# homeboard15.net
KiCad netlist of a schematic drawn in EAGLE
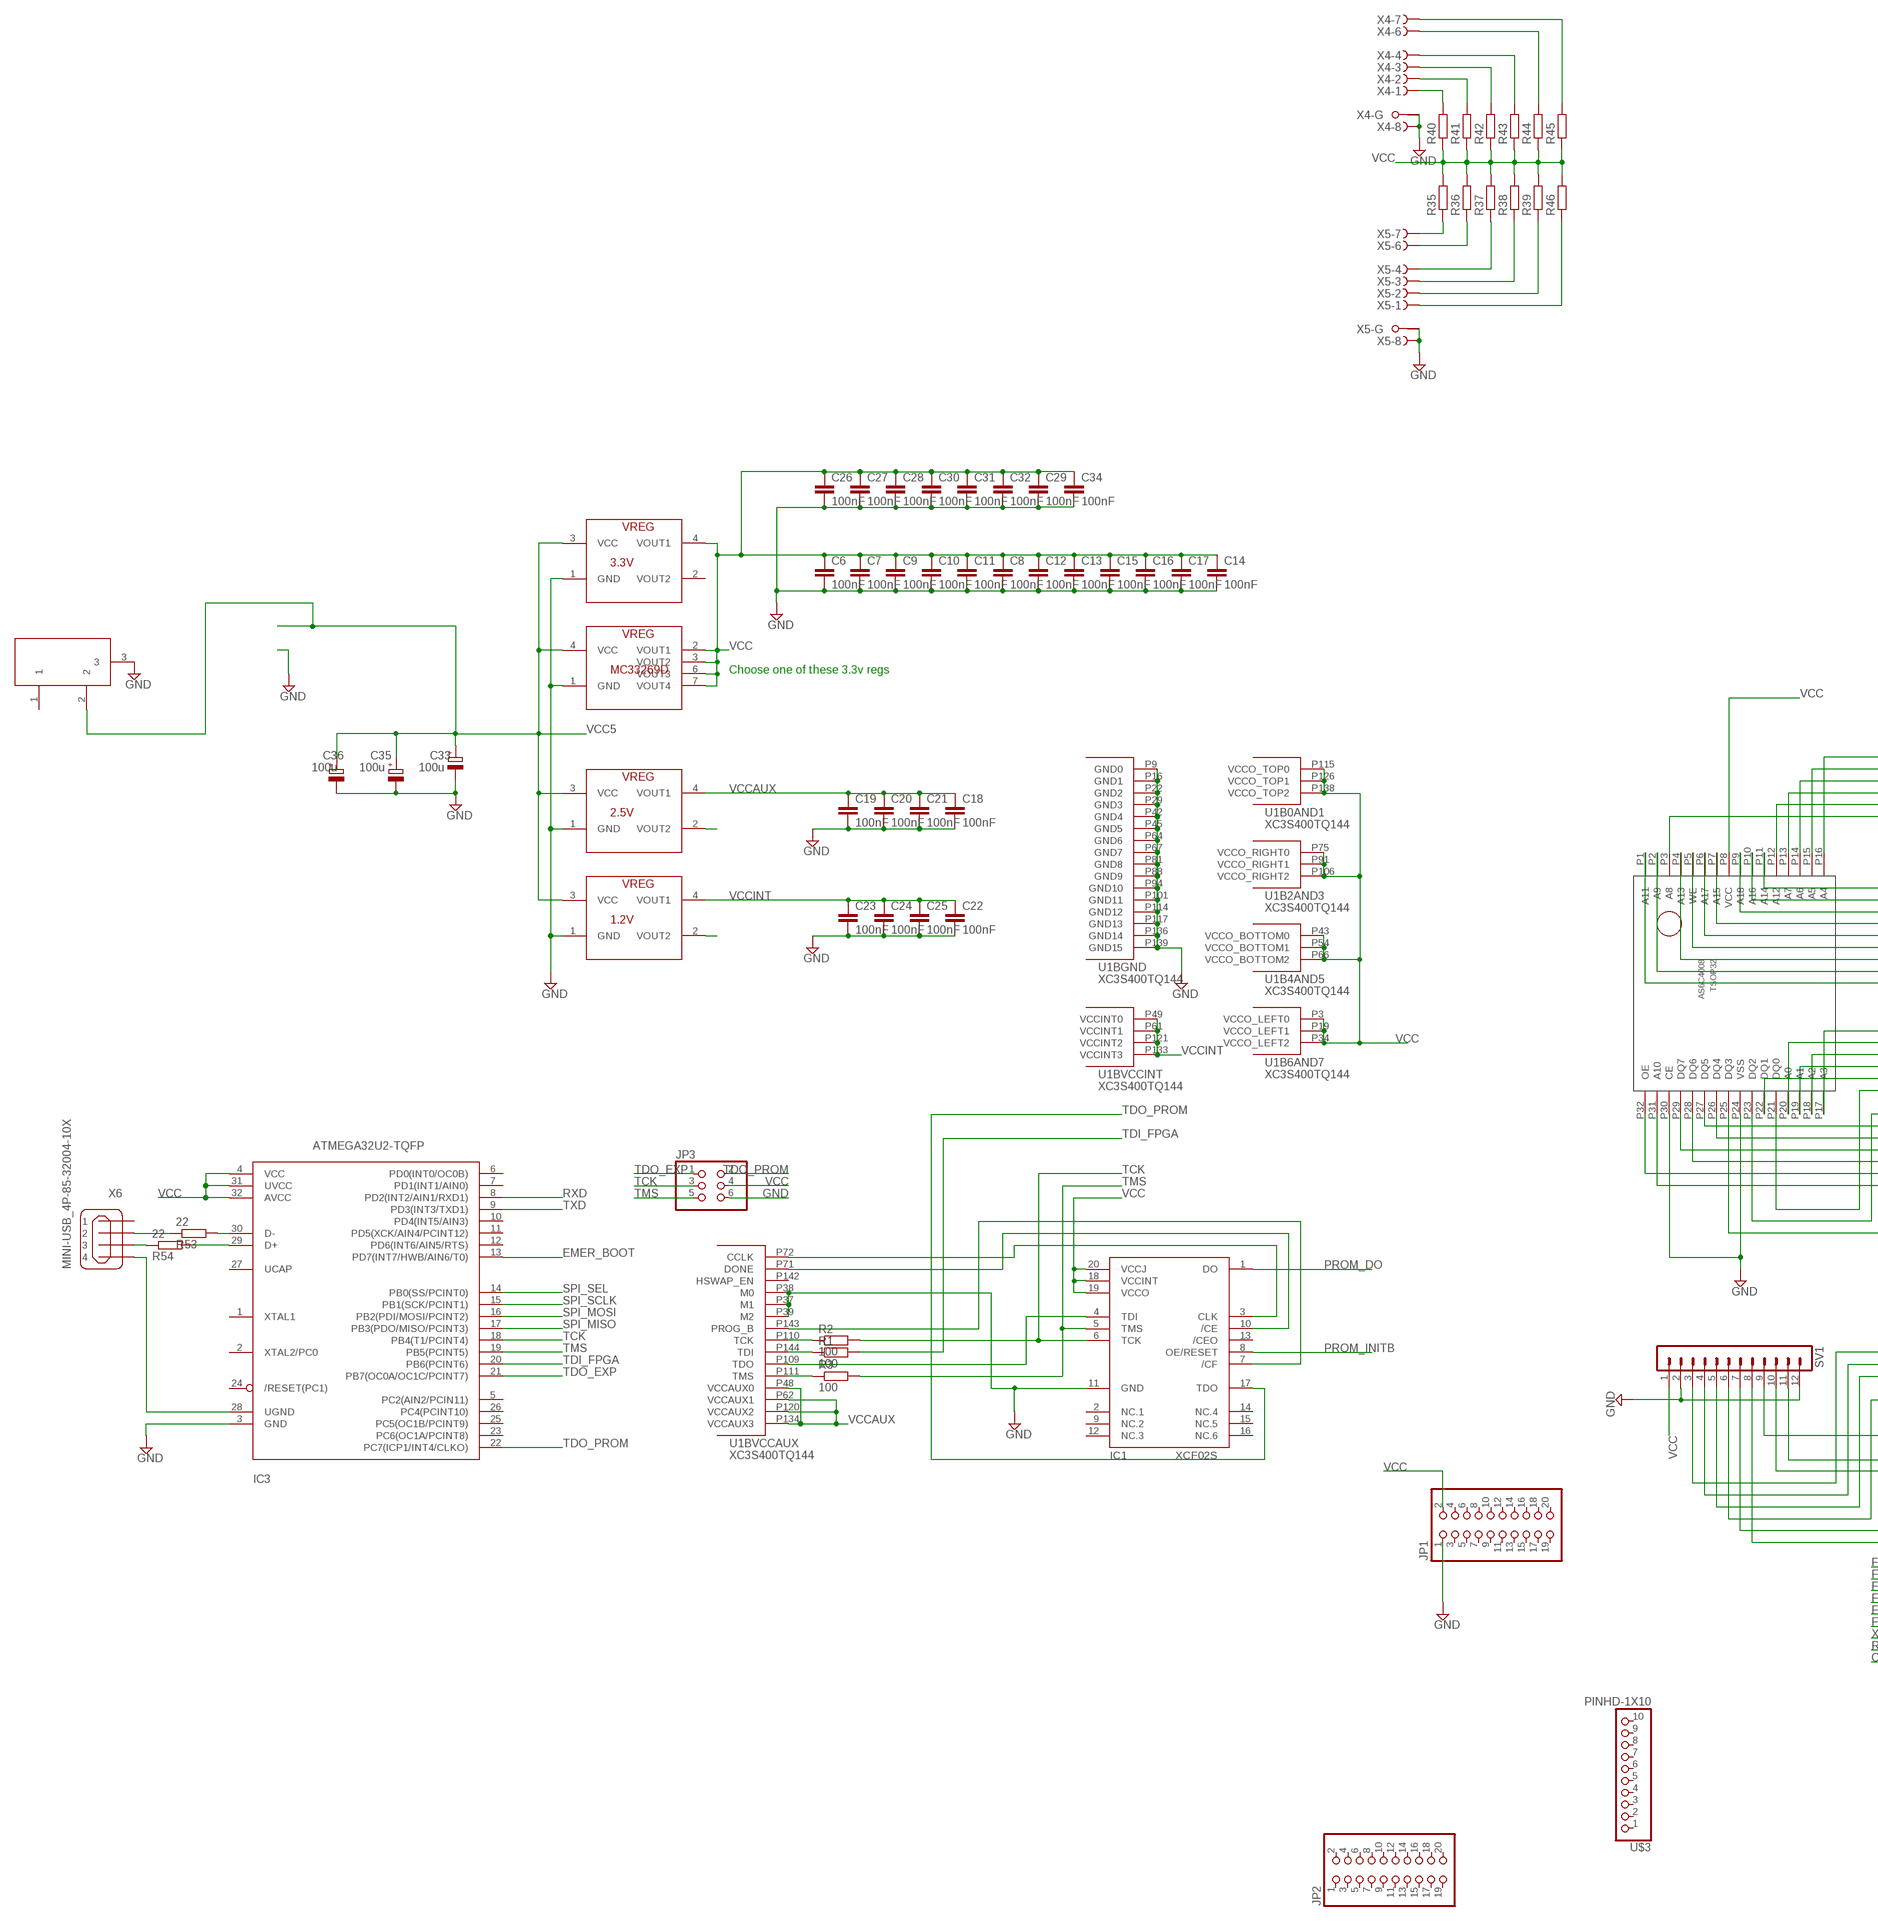
[diagram p0: schematic, sheet 1, part 1 of 3]
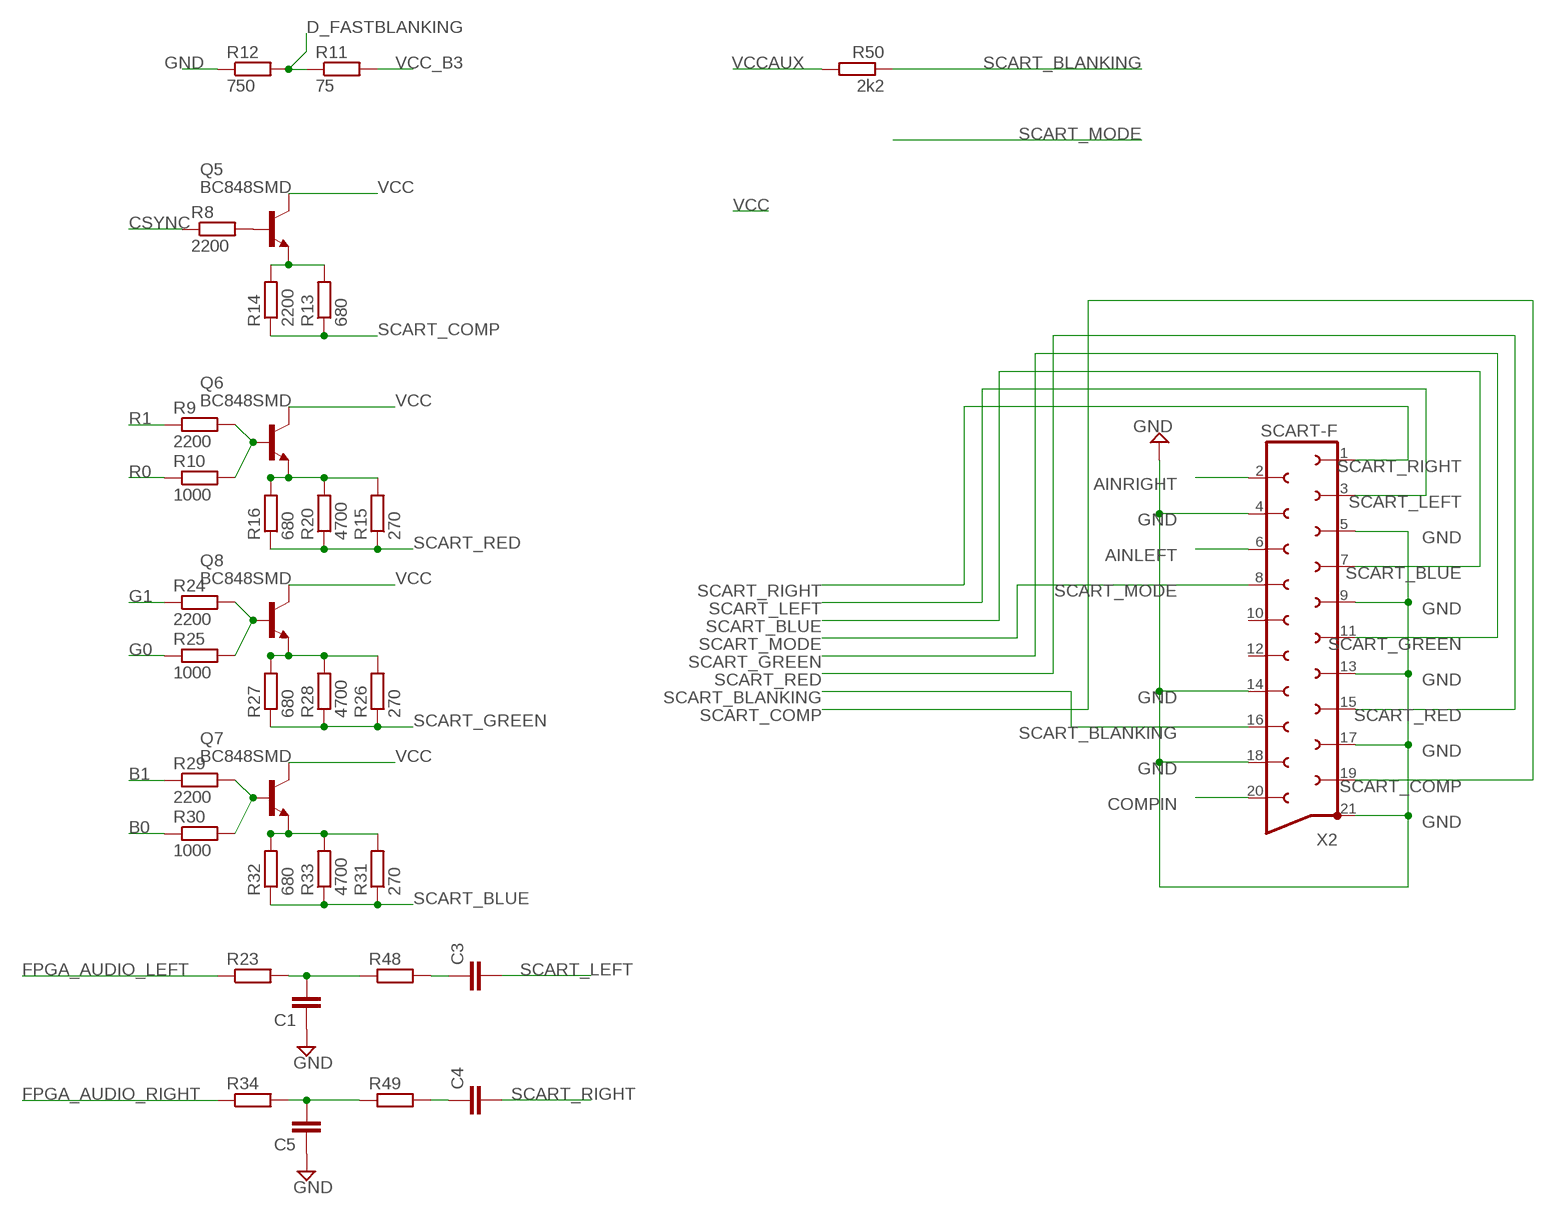
[diagram p1: schematic, sheet 1, part 2 of 3]
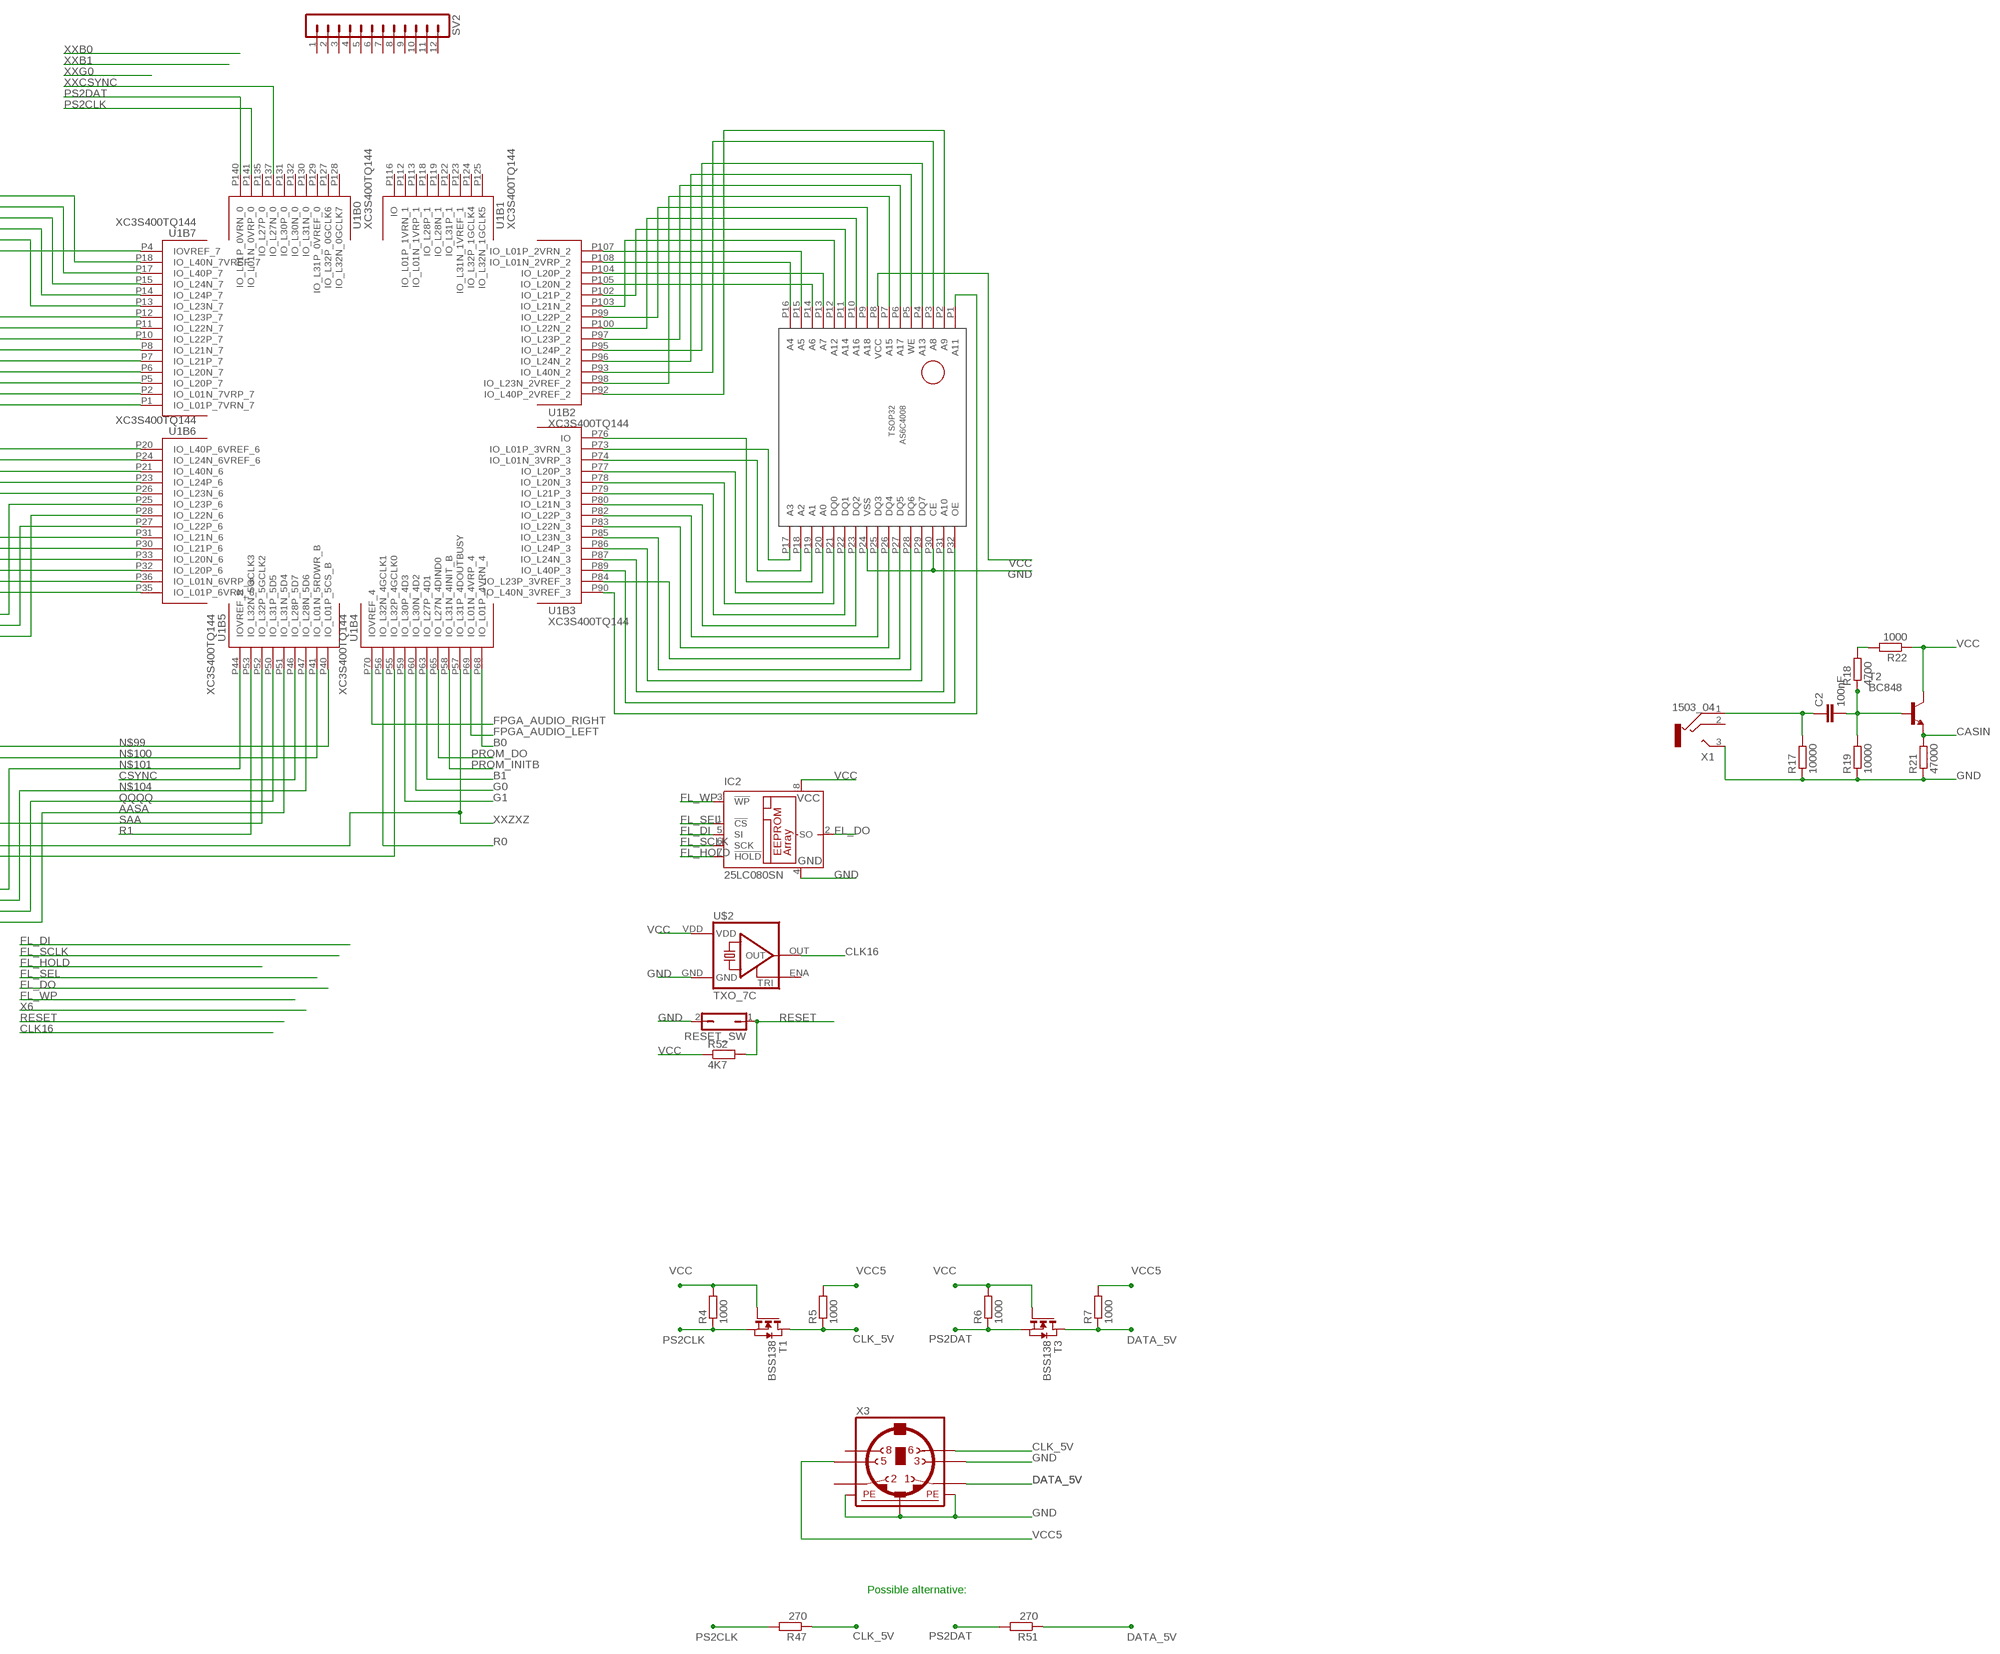
[diagram p2: schematic, sheet 1, part 3 of 3]

(export (version "E")
  (design (tool "Eeschema 10.0.6"))
  (components
    (comp (ref "C1")
      (value "C-EUC0603")
      (footprint "eagle-import:C0603")
      (libsource (lib "eagle-import") (part "resistor_C-EUC0603"))
    )
    (comp (ref "C2")
      (value "100nF")
      (footprint "eagle-import:C0603")
      (libsource (lib "eagle-import") (part "resistor_C-EUC0603"))
    )
    (comp (ref "C3")
      (value "C-EUC0603")
      (footprint "eagle-import:C0603")
      (libsource (lib "eagle-import") (part "resistor_C-EUC0603"))
    )
    (comp (ref "C4")
      (value "C-EUC0603")
      (footprint "eagle-import:C0603")
      (libsource (lib "eagle-import") (part "resistor_C-EUC0603"))
    )
    (comp (ref "C5")
      (value "C-EUC0603")
      (footprint "eagle-import:C0603")
      (libsource (lib "eagle-import") (part "resistor_C-EUC0603"))
    )
    (comp (ref "C6")
      (value "100nF")
      (footprint "eagle-import:C0603")
      (libsource (lib "eagle-import") (part "C-EUC0603"))
    )
    (comp (ref "C7")
      (value "100nF")
      (footprint "eagle-import:C0603")
      (libsource (lib "eagle-import") (part "C-EUC0603"))
    )
    (comp (ref "C8")
      (value "100nF")
      (footprint "eagle-import:C0603")
      (libsource (lib "eagle-import") (part "C-EUC0603"))
    )
    (comp (ref "C9")
      (value "100nF")
      (footprint "eagle-import:C0603")
      (libsource (lib "eagle-import") (part "C-EUC0603"))
    )
    (comp (ref "C10")
      (value "100nF")
      (footprint "eagle-import:C0603")
      (libsource (lib "eagle-import") (part "C-EUC0603"))
    )
    (comp (ref "C11")
      (value "100nF")
      (footprint "eagle-import:C0603")
      (libsource (lib "eagle-import") (part "C-EUC0603"))
    )
    (comp (ref "C12")
      (value "100nF")
      (footprint "eagle-import:C0603")
      (libsource (lib "eagle-import") (part "C-EUC0603"))
    )
    (comp (ref "C13")
      (value "100nF")
      (footprint "eagle-import:C0603")
      (libsource (lib "eagle-import") (part "C-EUC0603"))
    )
    (comp (ref "C14")
      (value "100nF")
      (footprint "eagle-import:C0603")
      (libsource (lib "eagle-import") (part "C-EUC0603"))
    )
    (comp (ref "C15")
      (value "100nF")
      (footprint "eagle-import:C0603")
      (libsource (lib "eagle-import") (part "C-EUC0603"))
    )
    (comp (ref "C16")
      (value "100nF")
      (footprint "eagle-import:C0603")
      (libsource (lib "eagle-import") (part "C-EUC0603"))
    )
    (comp (ref "C17")
      (value "100nF")
      (footprint "eagle-import:C0603")
      (libsource (lib "eagle-import") (part "C-EUC0603"))
    )
    (comp (ref "C18")
      (value "100nF")
      (footprint "eagle-import:C0603")
      (libsource (lib "eagle-import") (part "C-EUC0603"))
    )
    (comp (ref "C19")
      (value "100nF")
      (footprint "eagle-import:C0603")
      (libsource (lib "eagle-import") (part "C-EUC0603"))
    )
    (comp (ref "C20")
      (value "100nF")
      (footprint "eagle-import:C0603")
      (libsource (lib "eagle-import") (part "C-EUC0603"))
    )
    (comp (ref "C21")
      (value "100nF")
      (footprint "eagle-import:C0603")
      (libsource (lib "eagle-import") (part "C-EUC0603"))
    )
    (comp (ref "C22")
      (value "100nF")
      (footprint "eagle-import:C0603")
      (libsource (lib "eagle-import") (part "C-EUC0603"))
    )
    (comp (ref "C23")
      (value "100nF")
      (footprint "eagle-import:C0603")
      (libsource (lib "eagle-import") (part "C-EUC0603"))
    )
    (comp (ref "C24")
      (value "100nF")
      (footprint "eagle-import:C0603")
      (libsource (lib "eagle-import") (part "C-EUC0603"))
    )
    (comp (ref "C25")
      (value "100nF")
      (footprint "eagle-import:C0603")
      (libsource (lib "eagle-import") (part "C-EUC0603"))
    )
    (comp (ref "C26")
      (value "100nF")
      (footprint "eagle-import:C0603")
      (libsource (lib "eagle-import") (part "C-EUC0603"))
    )
    (comp (ref "C27")
      (value "100nF")
      (footprint "eagle-import:C0603")
      (libsource (lib "eagle-import") (part "C-EUC0603"))
    )
    (comp (ref "C28")
      (value "100nF")
      (footprint "eagle-import:C0603")
      (libsource (lib "eagle-import") (part "C-EUC0603"))
    )
    (comp (ref "C29")
      (value "100nF")
      (footprint "eagle-import:C0603")
      (libsource (lib "eagle-import") (part "C-EUC0603"))
    )
    (comp (ref "C30")
      (value "100nF")
      (footprint "eagle-import:C0603")
      (libsource (lib "eagle-import") (part "C-EUC0603"))
    )
    (comp (ref "C31")
      (value "100nF")
      (footprint "eagle-import:C0603")
      (libsource (lib "eagle-import") (part "C-EUC0603"))
    )
    (comp (ref "C32")
      (value "100nF")
      (footprint "eagle-import:C0603")
      (libsource (lib "eagle-import") (part "C-EUC0603"))
    )
    (comp (ref "C33")
      (value "100u")
      (footprint "eagle-import:PANASONIC_D")
      (libsource (lib "eagle-import") (part "CPOL-EUD"))
    )
    (comp (ref "C34")
      (value "100nF")
      (footprint "eagle-import:C0603")
      (libsource (lib "eagle-import") (part "C-EUC0603"))
    )
    (comp (ref "C35")
      (value "100u")
      (footprint "eagle-import:PANASONIC_D")
      (libsource (lib "eagle-import") (part "CPOL-EUD"))
    )
    (comp (ref "C36")
      (value "100u")
      (footprint "eagle-import:PANASONIC_D")
      (libsource (lib "eagle-import") (part "CPOL-EUD"))
    )
    (comp (ref "IC1")
      (value "XCF02S")
      (footprint "eagle-import:VO20")
      (libsource (lib "eagle-import") (part "XCF02S"))
    )
    (comp (ref "IC2")
      (value "25LC080SN")
      (footprint "eagle-import:SO-08")
      (fields (field (name "MF") "MICROCHIP") (field (name "MPN") "25LC080/SN"))
      (libsource (lib "eagle-import") (part "25SNLC080"))
    )
    (comp (ref "IC3")
      (value "ATMEGA32U2-TQFP")
      (footprint "eagle-import:TQFP32-08")
      (libsource (lib "eagle-import") (part "ATMEGA32U2-TQFP"))
    )
    (comp (ref "JP1")
      (value "PINHD-2X10")
      (footprint "eagle-import:2X10")
      (libsource (lib "eagle-import") (part "PINHD-2X10"))
    )
    (comp (ref "JP2")
      (value "PINHD-2X10")
      (footprint "eagle-import:2X10")
      (libsource (lib "eagle-import") (part "PINHD-2X10"))
    )
    (comp (ref "JP3")
      (value "PINHD-2X3")
      (footprint "eagle-import:2X03")
      (libsource (lib "eagle-import") (part "PINHD-2X3"))
    )
    (comp (ref "Q5")
      (value "BC848SMD")
      (footprint "eagle-import:SOT23")
      (libsource (lib "eagle-import") (part "BC848SMD"))
    )
    (comp (ref "Q6")
      (value "BC848SMD")
      (footprint "eagle-import:SOT23")
      (libsource (lib "eagle-import") (part "BC848SMD"))
    )
    (comp (ref "Q7")
      (value "BC848SMD")
      (footprint "eagle-import:SOT23")
      (libsource (lib "eagle-import") (part "BC848SMD"))
    )
    (comp (ref "Q8")
      (value "BC848SMD")
      (footprint "eagle-import:SOT23")
      (libsource (lib "eagle-import") (part "BC848SMD"))
    )
    (comp (ref "R1")
      (value "100")
      (footprint "eagle-import:R0805")
      (libsource (lib "eagle-import") (part "R-EU_R0805"))
    )
    (comp (ref "R2")
      (value "100")
      (footprint "eagle-import:R0805")
      (libsource (lib "eagle-import") (part "R-EU_R0805"))
    )
    (comp (ref "R3")
      (value "100")
      (footprint "eagle-import:R0805")
      (libsource (lib "eagle-import") (part "R-EU_R0805"))
    )
    (comp (ref "R4")
      (value "1000")
      (footprint "eagle-import:R0805")
      (libsource (lib "eagle-import") (part "R-EU_R0805"))
    )
    (comp (ref "R5")
      (value "1000")
      (footprint "eagle-import:R0805")
      (libsource (lib "eagle-import") (part "R-EU_R0805"))
    )
    (comp (ref "R6")
      (value "1000")
      (footprint "eagle-import:R0805")
      (libsource (lib "eagle-import") (part "R-EU_R0805"))
    )
    (comp (ref "R7")
      (value "1000")
      (footprint "eagle-import:R0805")
      (libsource (lib "eagle-import") (part "R-EU_R0805"))
    )
    (comp (ref "R8")
      (value "2200")
      (footprint "eagle-import:R0805")
      (libsource (lib "eagle-import") (part "R-EU_R0805"))
    )
    (comp (ref "R9")
      (value "2200")
      (footprint "eagle-import:R0805")
      (libsource (lib "eagle-import") (part "R-EU_R0805"))
    )
    (comp (ref "R10")
      (value "1000")
      (footprint "eagle-import:R0805")
      (libsource (lib "eagle-import") (part "R-EU_R0805"))
    )
    (comp (ref "R11")
      (value "75")
      (footprint "eagle-import:R0805")
      (libsource (lib "eagle-import") (part "R-EU_R0805"))
    )
    (comp (ref "R12")
      (value "750")
      (footprint "eagle-import:R0805")
      (libsource (lib "eagle-import") (part "R-EU_R0805"))
    )
    (comp (ref "R13")
      (value "680")
      (footprint "eagle-import:R0805")
      (libsource (lib "eagle-import") (part "R-EU_R0805"))
    )
    (comp (ref "R14")
      (value "2200")
      (footprint "eagle-import:R0805")
      (libsource (lib "eagle-import") (part "R-EU_R0805"))
    )
    (comp (ref "R15")
      (value "270")
      (footprint "eagle-import:R0805")
      (libsource (lib "eagle-import") (part "R-EU_R0805"))
    )
    (comp (ref "R16")
      (value "680")
      (footprint "eagle-import:R0805")
      (libsource (lib "eagle-import") (part "R-EU_R0805"))
    )
    (comp (ref "R17")
      (value "10000")
      (footprint "eagle-import:R0805")
      (libsource (lib "eagle-import") (part "R-EU_R0805"))
    )
    (comp (ref "R18")
      (value "4700")
      (footprint "eagle-import:R0805")
      (libsource (lib "eagle-import") (part "R-EU_R0805"))
    )
    (comp (ref "R19")
      (value "10000")
      (footprint "eagle-import:R0805")
      (libsource (lib "eagle-import") (part "R-EU_R0805"))
    )
    (comp (ref "R20")
      (value "4700")
      (footprint "eagle-import:R0805")
      (libsource (lib "eagle-import") (part "R-EU_R0805"))
    )
    (comp (ref "R21")
      (value "47000")
      (footprint "eagle-import:R0805")
      (libsource (lib "eagle-import") (part "R-EU_R0805"))
    )
    (comp (ref "R22")
      (value "1000")
      (footprint "eagle-import:R0805")
      (libsource (lib "eagle-import") (part "R-EU_R0805"))
    )
    (comp (ref "R23")
      (value "R-EU_M0805")
      (footprint "eagle-import:M0805")
      (libsource (lib "eagle-import") (part "resistor_R-EU_M0805"))
    )
    (comp (ref "R24")
      (value "2200")
      (footprint "eagle-import:R0805")
      (libsource (lib "eagle-import") (part "R-EU_R0805"))
    )
    (comp (ref "R25")
      (value "1000")
      (footprint "eagle-import:R0805")
      (libsource (lib "eagle-import") (part "R-EU_R0805"))
    )
    (comp (ref "R26")
      (value "270")
      (footprint "eagle-import:R0805")
      (libsource (lib "eagle-import") (part "R-EU_R0805"))
    )
    (comp (ref "R27")
      (value "680")
      (footprint "eagle-import:R0805")
      (libsource (lib "eagle-import") (part "R-EU_R0805"))
    )
    (comp (ref "R28")
      (value "4700")
      (footprint "eagle-import:R0805")
      (libsource (lib "eagle-import") (part "R-EU_R0805"))
    )
    (comp (ref "R29")
      (value "2200")
      (footprint "eagle-import:R0805")
      (libsource (lib "eagle-import") (part "R-EU_R0805"))
    )
    (comp (ref "R30")
      (value "1000")
      (footprint "eagle-import:R0805")
      (libsource (lib "eagle-import") (part "R-EU_R0805"))
    )
    (comp (ref "R31")
      (value "270")
      (footprint "eagle-import:R0805")
      (libsource (lib "eagle-import") (part "R-EU_R0805"))
    )
    (comp (ref "R32")
      (value "680")
      (footprint "eagle-import:R0805")
      (libsource (lib "eagle-import") (part "R-EU_R0805"))
    )
    (comp (ref "R33")
      (value "4700")
      (footprint "eagle-import:R0805")
      (libsource (lib "eagle-import") (part "R-EU_R0805"))
    )
    (comp (ref "R34")
      (value "R-EU_M0805")
      (footprint "eagle-import:M0805")
      (libsource (lib "eagle-import") (part "resistor_R-EU_M0805"))
    )
    (comp (ref "R35")
      (value "R-EU_M0805")
      (footprint "eagle-import:M0805")
      (libsource (lib "eagle-import") (part "resistor_R-EU_M0805"))
    )
    (comp (ref "R36")
      (value "R-EU_M0805")
      (footprint "eagle-import:M0805")
      (libsource (lib "eagle-import") (part "resistor_R-EU_M0805"))
    )
    (comp (ref "R37")
      (value "R-EU_M0805")
      (footprint "eagle-import:M0805")
      (libsource (lib "eagle-import") (part "resistor_R-EU_M0805"))
    )
    (comp (ref "R38")
      (value "R-EU_M0805")
      (footprint "eagle-import:M0805")
      (libsource (lib "eagle-import") (part "resistor_R-EU_M0805"))
    )
    (comp (ref "R39")
      (value "R-EU_M0805")
      (footprint "eagle-import:M0805")
      (libsource (lib "eagle-import") (part "resistor_R-EU_M0805"))
    )
    (comp (ref "R40")
      (value "R-EU_M0805")
      (footprint "eagle-import:M0805")
      (libsource (lib "eagle-import") (part "resistor_R-EU_M0805"))
    )
    (comp (ref "R41")
      (value "R-EU_M0805")
      (footprint "eagle-import:M0805")
      (libsource (lib "eagle-import") (part "resistor_R-EU_M0805"))
    )
    (comp (ref "R42")
      (value "R-EU_M0805")
      (footprint "eagle-import:M0805")
      (libsource (lib "eagle-import") (part "resistor_R-EU_M0805"))
    )
    (comp (ref "R43")
      (value "R-EU_M0805")
      (footprint "eagle-import:M0805")
      (libsource (lib "eagle-import") (part "resistor_R-EU_M0805"))
    )
    (comp (ref "R44")
      (value "R-EU_M0805")
      (footprint "eagle-import:M0805")
      (libsource (lib "eagle-import") (part "resistor_R-EU_M0805"))
    )
    (comp (ref "R45")
      (value "R-EU_M0805")
      (footprint "eagle-import:M0805")
      (libsource (lib "eagle-import") (part "resistor_R-EU_M0805"))
    )
    (comp (ref "R46")
      (value "R-EU_M0805")
      (footprint "eagle-import:M0805")
      (libsource (lib "eagle-import") (part "resistor_R-EU_M0805"))
    )
    (comp (ref "R47")
      (value "270")
      (footprint "eagle-import:R0805")
      (libsource (lib "eagle-import") (part "R-EU_R0805"))
    )
    (comp (ref "R48")
      (value "R-EU_M0805")
      (footprint "eagle-import:M0805")
      (libsource (lib "eagle-import") (part "resistor_R-EU_M0805"))
    )
    (comp (ref "R49")
      (value "R-EU_M0805")
      (footprint "eagle-import:M0805")
      (libsource (lib "eagle-import") (part "resistor_R-EU_M0805"))
    )
    (comp (ref "R50")
      (value "2k2")
      (footprint "eagle-import:M0805")
      (libsource (lib "eagle-import") (part "resistor_R-EU_M0805"))
    )
    (comp (ref "R51")
      (value "270")
      (footprint "eagle-import:R0805")
      (libsource (lib "eagle-import") (part "R-EU_R0805"))
    )
    (comp (ref "R52")
      (value "4K7")
      (footprint "eagle-import:M0805")
      (libsource (lib "eagle-import") (part "resistor_R-EU_M0805"))
    )
    (comp (ref "R53")
      (value "22")
      (footprint "eagle-import:R0805")
      (libsource (lib "eagle-import") (part "R-EU_R0805"))
    )
    (comp (ref "R54")
      (value "22")
      (footprint "eagle-import:R0805")
      (libsource (lib "eagle-import") (part "R-EU_R0805"))
    )
    (comp (ref "REG1.2")
      (value "1.2V")
      (footprint "eagle-import:SOT223")
      (libsource (lib "eagle-import") (part "NX1117"))
    )
    (comp (ref "REG2.5")
      (value "2.5V")
      (footprint "eagle-import:SOT223")
      (libsource (lib "eagle-import") (part "NX1117"))
    )
    (comp (ref "RESET_SW")
      (value "JP1Q")
      (footprint "eagle-import:JP1")
      (libsource (lib "eagle-import") (part "JP1Q"))
    )
    (comp (ref "SV1")
      (value "MA12-1")
      (footprint "eagle-import:MA12-1")
      (libsource (lib "eagle-import") (part "MA12-1"))
    )
    (comp (ref "SV2")
      (value "MA12-1")
      (footprint "eagle-import:MA12-1")
      (fields (field (name "OC_FARNELL") "unknown") (field (name "OC_NEWARK") "unknown"))
      (libsource (lib "eagle-import") (part "MA12-1"))
    )
    (comp (ref "T1")
      (value "BSS138")
      (footprint "eagle-import:SOT-23")
      (libsource (lib "eagle-import") (part "NMOSSOT23"))
    )
    (comp (ref "T2")
      (value "BC848")
      (footprint "eagle-import:SOT23")
      (libsource (lib "eagle-import") (part "BC848"))
    )
    (comp (ref "T3")
      (value "BSS138")
      (footprint "eagle-import:SOT-23")
      (libsource (lib "eagle-import") (part "NMOSSOT23"))
    )
    (comp (ref "U$1")
      (value "AS6C4008")
      (footprint "eagle-import:TSOP32")
      (libsource (lib "eagle-import") (part "AS6C4008"))
    )
    (comp (ref "U$2")
      (value "TXO_7C")
      (footprint "eagle-import:OSC_7C")
      (libsource (lib "eagle-import") (part "TXO_7C"))
    )
    (comp (ref "U$3")
      (value "PINHD-1X10")
      (footprint "eagle-import:1X10-BIG")
      (libsource (lib "eagle-import") (part "PINHD-1X10"))
    )
    (comp (ref "U$4")
      (value "3.3V")
      (footprint "eagle-import:SOT223")
      (libsource (lib "eagle-import") (part "NX1117"))
    )
    (comp (ref "U$5")
      (value "MC33269D")
      (footprint "eagle-import:SO8")
      (libsource (lib "eagle-import") (part "MC33269D"))
    )
    (comp (ref "U$6")
      (value "AS6C4008")
      (footprint "eagle-import:TSOP32")
      (libsource (lib "eagle-import") (part "AS6C4008"))
    )
    (comp (ref "U1")
      (value "XC3S400TQ144")
      (footprint "eagle-import:TQ144")
      (libsource (lib "eagle-import") (part "XC3S400TQ144"))
    )
    (comp (ref "X1")
      (value "1503_04")
      (footprint "eagle-import:1503_04")
      (libsource (lib "eagle-import") (part "1503_04"))
    )
    (comp (ref "X2")
      (value "SCART-F")
      (footprint "eagle-import:SCART-F")
      (libsource (lib "eagle-import") (part "SCART-F"))
    )
    (comp (ref "X3")
      (value "MINI_DIN_6")
      (footprint "eagle-import:M_DIN6")
      (libsource (lib "eagle-import") (part "MINI_DIN_6"))
    )
    (comp (ref "X4")
      (value "F09HPS")
      (footprint "eagle-import:F09HP")
      (libsource (lib "eagle-import") (part "F09HPS"))
    )
    (comp (ref "X5")
      (value "F09HPS")
      (footprint "eagle-import:F09HP")
      (libsource (lib "eagle-import") (part "F09HPS"))
    )
    (comp (ref "X6")
      (value "MINI-USB_4P-85-32004-10X")
      (footprint "eagle-import:85-32004-10X")
      (libsource (lib "eagle-import") (part "MINI-USB_4P-85-32004-10X"))
    )
    (comp (ref "X7")
      (value "DC21MMX")
      (footprint "eagle-import:DC-21MM")
      (libsource (lib "eagle-import") (part "DC21MMX"))
    )
  )
  (nets
    (net (code "1") (name "/1") (class "Default")
      (node (ref "X7") (pin "1") (pinfunction "1_1") (pintype "power_in"))
    )
    (net (code "2") (name "/AASA") (class "Default")
      (node (ref "SV1") (pin "8") (pinfunction "8_8") (pintype "passive"))
      (node (ref "U1") (pin "P51") (pinfunction "IO_L31N_5D4_P51") (pintype "bidirectional"))
    )
    (net (code "3") (name "/AINLEFT") (class "Default")
      (node (ref "X2") (pin "6") (pinfunction "6_6") (pintype "passive"))
    )
    (net (code "4") (name "/AINRIGHT") (class "Default")
      (node (ref "X2") (pin "2") (pinfunction "2_2") (pintype "passive"))
    )
    (net (code "5") (name "/B0") (class "Default")
      (node (ref "R30") (pin "1") (pinfunction "1_1") (pintype "passive"))
      (node (ref "U1") (pin "P68") (pinfunction "IO_L01P_4VRN_4_P68") (pintype "bidirectional"))
    )
    (net (code "6") (name "/B1") (class "Default")
      (node (ref "R29") (pin "1") (pinfunction "1_1") (pintype "passive"))
      (node (ref "U1") (pin "P63") (pinfunction "IO_L27P_4D1_P63") (pintype "bidirectional"))
    )
    (net (code "7") (name "/CASIN") (class "Default")
      (node (ref "R21") (pin "2") (pinfunction "2_2") (pintype "passive"))
      (node (ref "T2") (pin "2") (pinfunction "E_2") (pintype "passive"))
    )
    (net (code "8") (name "/CLK16") (class "Default")
      (node (ref "U$2") (pin "OUT") (pinfunction "OUT_OUT") (pintype "output"))
    )
    (net (code "9") (name "/CLK_5V") (class "Default")
      (node (ref "R47") (pin "1") (pinfunction "1_1") (pintype "passive"))
      (node (ref "R5") (pin "1") (pinfunction "1_1") (pintype "passive"))
      (node (ref "T1") (pin "1") (pinfunction "D_1") (pintype "passive"))
      (node (ref "X3") (pin "6") (pinfunction "6_6") (pintype "passive"))
    )
    (net (code "10") (name "/COMPIN") (class "Default")
      (node (ref "X2") (pin "20") (pinfunction "20_20") (pintype "passive"))
    )
    (net (code "11") (name "/CSYNC") (class "Default")
      (node (ref "R8") (pin "1") (pinfunction "1_1") (pintype "passive"))
      (node (ref "U1") (pin "P46") (pinfunction "IO_L28P_5D7_P46") (pintype "bidirectional"))
    )
    (net (code "12") (name "/DATA_5V") (class "Default")
      (node (ref "R51") (pin "1") (pinfunction "1_1") (pintype "passive"))
      (node (ref "R7") (pin "1") (pinfunction "1_1") (pintype "passive"))
      (node (ref "T3") (pin "1") (pinfunction "D_1") (pintype "passive"))
      (node (ref "X3") (pin "1") (pinfunction "1_1") (pintype "passive"))
    )
    (net (code "13") (name "/D_FASTBLANKING") (class "Default")
      (node (ref "R11") (pin "1") (pinfunction "1_1") (pintype "passive"))
      (node (ref "R12") (pin "2") (pinfunction "2_2") (pintype "passive"))
    )
    (net (code "14") (name "/EMER_BOOT") (class "Default")
      (node (ref "IC3") (pin "13") (pinfunction "PD7(INT7/HWB/AIN6/T0)_13") (pintype "bidirectional"))
    )
    (net (code "15") (name "/FL_DI") (class "Default")
      (node (ref "IC2") (pin "5") (pinfunction "SI_5") (pintype "input"))
    )
    (net (code "16") (name "/FL_DO") (class "Default")
      (node (ref "IC2") (pin "2") (pinfunction "SO_2") (pintype "bidirectional"))
    )
    (net (code "17") (name "/FL_HOLD") (class "Default")
      (node (ref "IC2") (pin "7") (pinfunction "~{HOLD}_7") (pintype "input"))
    )
    (net (code "18") (name "/FL_SCLK") (class "Default")
      (node (ref "IC2") (pin "6") (pinfunction "SCK_6") (pintype "input"))
    )
    (net (code "19") (name "/FL_SEL") (class "Default")
      (node (ref "IC2") (pin "1") (pinfunction "~{CS}_1") (pintype "input"))
    )
    (net (code "20") (name "/FL_WP") (class "Default")
      (node (ref "IC2") (pin "3") (pinfunction "~{WP}_3") (pintype "input"))
    )
    (net (code "21") (name "/FPGA_AUDIO_LEFT") (class "Default")
      (node (ref "R23") (pin "1") (pinfunction "1_1") (pintype "passive"))
      (node (ref "U1") (pin "P69") (pinfunction "IO_L01N_4VRP_4_P69") (pintype "bidirectional"))
    )
    (net (code "22") (name "/FPGA_AUDIO_RIGHT") (class "Default")
      (node (ref "R34") (pin "1") (pinfunction "1_1") (pintype "passive"))
      (node (ref "U1") (pin "P70") (pinfunction "IOVREF_4_P70") (pintype "bidirectional"))
    )
    (net (code "23") (name "/G0") (class "Default")
      (node (ref "R25") (pin "1") (pinfunction "1_1") (pintype "passive"))
      (node (ref "U1") (pin "P60") (pinfunction "IO_L30N_4D2_P60") (pintype "bidirectional"))
    )
    (net (code "24") (name "/G1") (class "Default")
      (node (ref "R24") (pin "1") (pinfunction "1_1") (pintype "passive"))
      (node (ref "U1") (pin "P59") (pinfunction "IO_L30P_4D3_P59") (pintype "bidirectional"))
    )
    (net (code "25") (name "/N$99") (class "Default")
      (node (ref "SV1") (pin "3") (pinfunction "3_3") (pintype "passive"))
      (node (ref "U1") (pin "P40") (pinfunction "IO_L01P_5CS_B_P40") (pintype "bidirectional"))
    )
    (net (code "26") (name "/N$100") (class "Default")
      (node (ref "SV1") (pin "4") (pinfunction "4_4") (pintype "passive"))
      (node (ref "U1") (pin "P41") (pinfunction "IO_L01N_5RDWR_B_P41") (pintype "bidirectional"))
    )
    (net (code "27") (name "/N$101") (class "Default")
      (node (ref "SV1") (pin "5") (pinfunction "5_5") (pintype "passive"))
      (node (ref "U1") (pin "P44") (pinfunction "IOVREF_5_P44") (pintype "bidirectional"))
    )
    (net (code "28") (name "/N$104") (class "Default")
      (node (ref "SV1") (pin "6") (pinfunction "6_6") (pintype "passive"))
      (node (ref "U1") (pin "P47") (pinfunction "IO_L28N_5D6_P47") (pintype "bidirectional"))
    )
    (net (code "29") (name "/PROM_DO") (class "Default")
      (node (ref "IC1") (pin "1") (pinfunction "DO_1") (pintype "bidirectional"))
      (node (ref "U1") (pin "P65") (pinfunction "IO_L27N_4DIND0_P65") (pintype "bidirectional"))
    )
    (net (code "30") (name "/PROM_INITB") (class "Default")
      (node (ref "IC1") (pin "8") (pinfunction "OE/RESET_8") (pintype "bidirectional"))
      (node (ref "U1") (pin "P58") (pinfunction "IO_L31N_4INIT_B_P58") (pintype "bidirectional"))
    )
    (net (code "31") (name "/PS2CLK") (class "Default")
      (node (ref "R4") (pin "1") (pinfunction "1_1") (pintype "passive"))
      (node (ref "R47") (pin "2") (pinfunction "2_2") (pintype "passive"))
      (node (ref "T1") (pin "2") (pinfunction "S_2") (pintype "passive"))
      (node (ref "U1") (pin "P141") (pinfunction "IO_L01N_0VRP_0_P141") (pintype "bidirectional"))
    )
    (net (code "32") (name "/PS2DAT") (class "Default")
      (node (ref "R51") (pin "2") (pinfunction "2_2") (pintype "passive"))
      (node (ref "R6") (pin "1") (pinfunction "1_1") (pintype "passive"))
      (node (ref "T3") (pin "2") (pinfunction "S_2") (pintype "passive"))
      (node (ref "U1") (pin "P140") (pinfunction "IO_L01P_0VRN_0_P140") (pintype "bidirectional"))
    )
    (net (code "33") (name "/QQQQ") (class "Default")
      (node (ref "SV1") (pin "7") (pinfunction "7_7") (pintype "passive"))
      (node (ref "U1") (pin "P50") (pinfunction "IO_L31P_5D5_P50") (pintype "bidirectional"))
    )
    (net (code "34") (name "/R0") (class "Default")
      (node (ref "R10") (pin "1") (pinfunction "1_1") (pintype "passive"))
      (node (ref "U1") (pin "P56") (pinfunction "IO_L32N_4GCLK1_P56") (pintype "bidirectional"))
    )
    (net (code "35") (name "/R1") (class "Default")
      (node (ref "R9") (pin "1") (pinfunction "1_1") (pintype "passive"))
      (node (ref "U1") (pin "P53") (pinfunction "IO_L32N_5GCLK3_P53") (pintype "bidirectional"))
    )
    (net (code "36") (name "/RESET") (class "Default")
      (node (ref "R52") (pin "2") (pinfunction "2_2") (pintype "passive"))
      (node (ref "RESET_SW") (pin "1") (pinfunction "1_1") (pintype "passive"))
    )
    (net (code "37") (name "/RXD") (class "Default")
      (node (ref "IC3") (pin "8") (pinfunction "PD2(INT2/AIN1/RXD1)_8") (pintype "bidirectional"))
    )
    (net (code "38") (name "/SAA") (class "Default")
      (node (ref "SV1") (pin "9") (pinfunction "9_9") (pintype "passive"))
      (node (ref "U1") (pin "P52") (pinfunction "IO_L32P_5GCLK2_P52") (pintype "bidirectional"))
    )
    (net (code "39") (name "/SCART_BLANKING") (class "Default")
      (node (ref "R50") (pin "1") (pinfunction "1_1") (pintype "passive"))
      (node (ref "X2") (pin "16") (pinfunction "16_16") (pintype "passive"))
    )
    (net (code "40") (name "/SCART_BLUE") (class "Default")
      (node (ref "R31") (pin "1") (pinfunction "1_1") (pintype "passive"))
      (node (ref "R32") (pin "1") (pinfunction "1_1") (pintype "passive"))
      (node (ref "R33") (pin "1") (pinfunction "1_1") (pintype "passive"))
      (node (ref "X2") (pin "7") (pinfunction "7_7") (pintype "passive"))
    )
    (net (code "41") (name "/SCART_COMP") (class "Default")
      (node (ref "R13") (pin "1") (pinfunction "1_1") (pintype "passive"))
      (node (ref "R14") (pin "1") (pinfunction "1_1") (pintype "passive"))
      (node (ref "X2") (pin "19") (pinfunction "19_19") (pintype "passive"))
    )
    (net (code "42") (name "/SCART_GREEN") (class "Default")
      (node (ref "R26") (pin "1") (pinfunction "1_1") (pintype "passive"))
      (node (ref "R27") (pin "1") (pinfunction "1_1") (pintype "passive"))
      (node (ref "R28") (pin "1") (pinfunction "1_1") (pintype "passive"))
      (node (ref "X2") (pin "11") (pinfunction "11_11") (pintype "passive"))
    )
    (net (code "43") (name "/SCART_LEFT") (class "Default")
      (node (ref "C3") (pin "2") (pinfunction "2_2") (pintype "passive"))
      (node (ref "X2") (pin "3") (pinfunction "3_3") (pintype "passive"))
    )
    (net (code "44") (name "/SCART_MODE") (class "Default")
      (node (ref "X2") (pin "8") (pinfunction "8_8") (pintype "passive"))
    )
    (net (code "45") (name "/SCART_RED") (class "Default")
      (node (ref "R15") (pin "1") (pinfunction "1_1") (pintype "passive"))
      (node (ref "R16") (pin "1") (pinfunction "1_1") (pintype "passive"))
      (node (ref "R20") (pin "1") (pinfunction "1_1") (pintype "passive"))
      (node (ref "X2") (pin "15") (pinfunction "15_15") (pintype "passive"))
    )
    (net (code "46") (name "/SCART_RIGHT") (class "Default")
      (node (ref "C4") (pin "2") (pinfunction "2_2") (pintype "passive"))
      (node (ref "X2") (pin "1") (pinfunction "1_1") (pintype "passive"))
    )
    (net (code "47") (name "/SPI_MISO") (class "Default")
      (node (ref "IC3") (pin "17") (pinfunction "PB3(PDO/MISO/PCINT3)_17") (pintype "bidirectional"))
    )
    (net (code "48") (name "/SPI_MOSI") (class "Default")
      (node (ref "IC3") (pin "16") (pinfunction "PB2(PDI/MOSI/PCINT2)_16") (pintype "bidirectional"))
    )
    (net (code "49") (name "/SPI_SCLK") (class "Default")
      (node (ref "IC3") (pin "15") (pinfunction "PB1(SCK/PCINT1)_15") (pintype "bidirectional"))
    )
    (net (code "50") (name "/SPI_SEL") (class "Default")
      (node (ref "IC3") (pin "14") (pinfunction "PB0(SS/PCINT0)_14") (pintype "bidirectional"))
    )
    (net (code "51") (name "/TCK") (class "Default")
      (node (ref "IC1") (pin "6") (pinfunction "TCK_6") (pintype "bidirectional"))
      (node (ref "IC3") (pin "18") (pinfunction "PB4(T1/PCINT4)_18") (pintype "bidirectional"))
      (node (ref "JP3") (pin "3") (pinfunction "3_3") (pintype "passive"))
      (node (ref "R2") (pin "2") (pinfunction "2_2") (pintype "passive"))
    )
    (net (code "52") (name "/TDI_FPGA") (class "Default")
      (node (ref "IC3") (pin "20") (pinfunction "PB6(PCINT6)_20") (pintype "bidirectional"))
      (node (ref "R1") (pin "2") (pinfunction "2_2") (pintype "passive"))
    )
    (net (code "53") (name "/TDO_EXP") (class "Default")
      (node (ref "IC3") (pin "21") (pinfunction "PB7(OC0A/OC1C/PCINT7)_21") (pintype "bidirectional"))
      (node (ref "JP3") (pin "1") (pinfunction "1_1") (pintype "passive"))
    )
    (net (code "54") (name "/TDO_PROM") (class "Default")
      (node (ref "IC1") (pin "17") (pinfunction "TDO_17") (pintype "bidirectional"))
      (node (ref "IC3") (pin "22") (pinfunction "PC7(ICP1/INT4/CLKO)_22") (pintype "bidirectional"))
      (node (ref "JP3") (pin "2") (pinfunction "2_2") (pintype "passive"))
    )
    (net (code "55") (name "/TMS") (class "Default")
      (node (ref "IC1") (pin "5") (pinfunction "TMS_5") (pintype "bidirectional"))
      (node (ref "IC3") (pin "19") (pinfunction "PB5(PCINT5)_19") (pintype "bidirectional"))
      (node (ref "JP3") (pin "5") (pinfunction "5_5") (pintype "passive"))
      (node (ref "R3") (pin "2") (pinfunction "2_2") (pintype "passive"))
    )
    (net (code "56") (name "/TXD") (class "Default")
      (node (ref "IC3") (pin "9") (pinfunction "PD3(INT3/TXD1)_9") (pintype "bidirectional"))
    )
    (net (code "57") (name "/VCC") (class "Default")
      (node (ref "C10") (pin "1") (pinfunction "1_1") (pintype "passive"))
      (node (ref "C11") (pin "1") (pinfunction "1_1") (pintype "passive"))
      (node (ref "C12") (pin "1") (pinfunction "1_1") (pintype "passive"))
      (node (ref "C13") (pin "1") (pinfunction "1_1") (pintype "passive"))
      (node (ref "C14") (pin "1") (pinfunction "1_1") (pintype "passive"))
      (node (ref "C15") (pin "1") (pinfunction "1_1") (pintype "passive"))
      (node (ref "C16") (pin "1") (pinfunction "1_1") (pintype "passive"))
      (node (ref "C17") (pin "1") (pinfunction "1_1") (pintype "passive"))
      (node (ref "C26") (pin "1") (pinfunction "1_1") (pintype "passive"))
      (node (ref "C27") (pin "1") (pinfunction "1_1") (pintype "passive"))
      (node (ref "C28") (pin "1") (pinfunction "1_1") (pintype "passive"))
      (node (ref "C29") (pin "1") (pinfunction "1_1") (pintype "passive"))
      (node (ref "C30") (pin "1") (pinfunction "1_1") (pintype "passive"))
      (node (ref "C31") (pin "1") (pinfunction "1_1") (pintype "passive"))
      (node (ref "C32") (pin "1") (pinfunction "1_1") (pintype "passive"))
      (node (ref "C34") (pin "1") (pinfunction "1_1") (pintype "passive"))
      (node (ref "C6") (pin "1") (pinfunction "1_1") (pintype "passive"))
      (node (ref "C7") (pin "1") (pinfunction "1_1") (pintype "passive"))
      (node (ref "C8") (pin "1") (pinfunction "1_1") (pintype "passive"))
      (node (ref "C9") (pin "1") (pinfunction "1_1") (pintype "passive"))
      (node (ref "IC1") (pin "18") (pinfunction "VCCINT_18") (pintype "bidirectional"))
      (node (ref "IC1") (pin "19") (pinfunction "VCCO_19") (pintype "bidirectional"))
      (node (ref "IC1") (pin "20") (pinfunction "VCCJ_20") (pintype "bidirectional"))
      (node (ref "IC2") (pin "8") (pinfunction "VCC_8") (pintype "power_in"))
      (node (ref "IC3") (pin "31") (pinfunction "UVCC_31") (pintype "bidirectional"))
      (node (ref "IC3") (pin "32") (pinfunction "AVCC_32") (pintype "bidirectional"))
      (node (ref "IC3") (pin "4") (pinfunction "VCC_4") (pintype "bidirectional"))
      (node (ref "JP1") (pin "2") (pinfunction "2_2") (pintype "passive"))
      (node (ref "JP3") (pin "4") (pinfunction "4_4") (pintype "passive"))
      (node (ref "Q5") (pin "3") (pinfunction "C_3") (pintype "passive"))
      (node (ref "Q6") (pin "3") (pinfunction "C_3") (pintype "passive"))
      (node (ref "Q7") (pin "3") (pinfunction "C_3") (pintype "passive"))
      (node (ref "Q8") (pin "3") (pinfunction "C_3") (pintype "passive"))
      (node (ref "R22") (pin "1") (pinfunction "1_1") (pintype "passive"))
      (node (ref "R35") (pin "2") (pinfunction "2_2") (pintype "passive"))
      (node (ref "R36") (pin "2") (pinfunction "2_2") (pintype "passive"))
      (node (ref "R37") (pin "2") (pinfunction "2_2") (pintype "passive"))
      (node (ref "R38") (pin "2") (pinfunction "2_2") (pintype "passive"))
      (node (ref "R39") (pin "2") (pinfunction "2_2") (pintype "passive"))
      (node (ref "R4") (pin "2") (pinfunction "2_2") (pintype "passive"))
      (node (ref "R40") (pin "1") (pinfunction "1_1") (pintype "passive"))
      (node (ref "R41") (pin "1") (pinfunction "1_1") (pintype "passive"))
      (node (ref "R42") (pin "1") (pinfunction "1_1") (pintype "passive"))
      (node (ref "R43") (pin "1") (pinfunction "1_1") (pintype "passive"))
      (node (ref "R44") (pin "1") (pinfunction "1_1") (pintype "passive"))
      (node (ref "R45") (pin "1") (pinfunction "1_1") (pintype "passive"))
      (node (ref "R46") (pin "2") (pinfunction "2_2") (pintype "passive"))
      (node (ref "R52") (pin "1") (pinfunction "1_1") (pintype "passive"))
      (node (ref "R6") (pin "2") (pinfunction "2_2") (pintype "passive"))
      (node (ref "SV1") (pin "1") (pinfunction "1_1") (pintype "passive"))
      (node (ref "T1") (pin "3") (pinfunction "G_3") (pintype "passive"))
      (node (ref "T2") (pin "3") (pinfunction "C_3") (pintype "passive"))
      (node (ref "T3") (pin "3") (pinfunction "G_3") (pintype "passive"))
      (node (ref "U$1") (pin "P8") (pinfunction "VCC_P8") (pintype "bidirectional"))
      (node (ref "U$2") (pin "VDD") (pinfunction "VDD_VDD") (pintype "power_in"))
      (node (ref "U$4") (pin "4") (pinfunction "VOUT1_4") (pintype "bidirectional"))
      (node (ref "U$5") (pin "2") (pinfunction "VOUT1_2") (pintype "output"))
      (node (ref "U$5") (pin "3") (pinfunction "VOUT2_3") (pintype "output"))
      (node (ref "U$5") (pin "6") (pinfunction "VOUT3_6") (pintype "output"))
      (node (ref "U$5") (pin "7") (pinfunction "VOUT4_7") (pintype "output"))
      (node (ref "U$6") (pin "P8") (pinfunction "VCC_P8") (pintype "bidirectional"))
      (node (ref "U1") (pin "P106") (pinfunction "VCCO_RIGHT2_P106") (pintype "passive"))
      (node (ref "U1") (pin "P115") (pinfunction "VCCO_TOP0_P115") (pintype "passive"))
      (node (ref "U1") (pin "P126") (pinfunction "VCCO_TOP1_P126") (pintype "passive"))
      (node (ref "U1") (pin "P138") (pinfunction "VCCO_TOP2_P138") (pintype "passive"))
      (node (ref "U1") (pin "P19") (pinfunction "VCCO_LEFT1_P19") (pintype "passive"))
      (node (ref "U1") (pin "P3") (pinfunction "VCCO_LEFT0_P3") (pintype "passive"))
      (node (ref "U1") (pin "P34") (pinfunction "VCCO_LEFT2_P34") (pintype "passive"))
      (node (ref "U1") (pin "P43") (pinfunction "VCCO_BOTTOM0_P43") (pintype "passive"))
      (node (ref "U1") (pin "P54") (pinfunction "VCCO_BOTTOM1_P54") (pintype "passive"))
      (node (ref "U1") (pin "P66") (pinfunction "VCCO_BOTTOM2_P66") (pintype "passive"))
      (node (ref "U1") (pin "P75") (pinfunction "VCCO_RIGHT0_P75") (pintype "passive"))
      (node (ref "U1") (pin "P91") (pinfunction "VCCO_RIGHT1_P91") (pintype "passive"))
    )
    (net (code "58") (name "/VCC5") (class "Default")
      (node (ref "C33") (pin "+") (pinfunction "+_+") (pintype "passive"))
      (node (ref "C35") (pin "+") (pinfunction "+_+") (pintype "passive"))
      (node (ref "C36") (pin "+") (pinfunction "+_+") (pintype "passive"))
      (node (ref "R5") (pin "2") (pinfunction "2_2") (pintype "passive"))
      (node (ref "R7") (pin "2") (pinfunction "2_2") (pintype "passive"))
      (node (ref "REG1.2") (pin "3") (pinfunction "VCC_3") (pintype "bidirectional"))
      (node (ref "REG2.5") (pin "3") (pinfunction "VCC_3") (pintype "bidirectional"))
      (node (ref "U$4") (pin "3") (pinfunction "VCC_3") (pintype "bidirectional"))
      (node (ref "U$5") (pin "4") (pinfunction "VCC_4") (pintype "bidirectional"))
      (node (ref "X3") (pin "5") (pinfunction "5_5") (pintype "passive"))
      (node (ref "X7") (pin "2") (pinfunction "2_2") (pintype "power_in"))
    )
    (net (code "59") (name "/VCCAUX") (class "Default")
      (node (ref "C18") (pin "1") (pinfunction "1_1") (pintype "passive"))
      (node (ref "C19") (pin "1") (pinfunction "1_1") (pintype "passive"))
      (node (ref "C20") (pin "1") (pinfunction "1_1") (pintype "passive"))
      (node (ref "C21") (pin "1") (pinfunction "1_1") (pintype "passive"))
      (node (ref "R50") (pin "2") (pinfunction "2_2") (pintype "passive"))
      (node (ref "REG2.5") (pin "4") (pinfunction "VOUT1_4") (pintype "bidirectional"))
      (node (ref "U1") (pin "P120") (pinfunction "VCCAUX2_P120") (pintype "passive"))
      (node (ref "U1") (pin "P134") (pinfunction "VCCAUX3_P134") (pintype "passive"))
      (node (ref "U1") (pin "P48") (pinfunction "VCCAUX0_P48") (pintype "passive"))
      (node (ref "U1") (pin "P62") (pinfunction "VCCAUX1_P62") (pintype "passive"))
    )
    (net (code "60") (name "/VCCINT") (class "Default")
      (node (ref "C22") (pin "1") (pinfunction "1_1") (pintype "passive"))
      (node (ref "C23") (pin "1") (pinfunction "1_1") (pintype "passive"))
      (node (ref "C24") (pin "1") (pinfunction "1_1") (pintype "passive"))
      (node (ref "C25") (pin "1") (pinfunction "1_1") (pintype "passive"))
      (node (ref "REG1.2") (pin "4") (pinfunction "VOUT1_4") (pintype "bidirectional"))
      (node (ref "U1") (pin "P121") (pinfunction "VCCINT2_P121") (pintype "passive"))
      (node (ref "U1") (pin "P133") (pinfunction "VCCINT3_P133") (pintype "passive"))
      (node (ref "U1") (pin "P49") (pinfunction "VCCINT0_P49") (pintype "passive"))
      (node (ref "U1") (pin "P61") (pinfunction "VCCINT1_P61") (pintype "passive"))
    )
    (net (code "61") (name "/VCC_B3") (class "Default")
      (node (ref "R11") (pin "2") (pinfunction "2_2") (pintype "passive"))
    )
    (net (code "65") (name "/XXCSYNC") (class "Default")
      (node (ref "U1") (pin "P137") (pinfunction "IO_L27N_0_P137") (pintype "bidirectional"))
    )
    (net (code "67") (name "/XXZXZ") (class "Default")
      (node (ref "SV1") (pin "11") (pinfunction "11_11") (pintype "passive"))
      (node (ref "U1") (pin "P57") (pinfunction "IO_L31P_4DOUTBUSY_P57") (pintype "bidirectional"))
    )
    (net (code "68") (name "GND") (class "Default")
      (node (ref "C1") (pin "1") (pinfunction "1_1") (pintype "passive"))
      (node (ref "C10") (pin "2") (pinfunction "2_2") (pintype "passive"))
      (node (ref "C11") (pin "2") (pinfunction "2_2") (pintype "passive"))
      (node (ref "C12") (pin "2") (pinfunction "2_2") (pintype "passive"))
      (node (ref "C13") (pin "2") (pinfunction "2_2") (pintype "passive"))
      (node (ref "C14") (pin "2") (pinfunction "2_2") (pintype "passive"))
      (node (ref "C15") (pin "2") (pinfunction "2_2") (pintype "passive"))
      (node (ref "C16") (pin "2") (pinfunction "2_2") (pintype "passive"))
      (node (ref "C17") (pin "2") (pinfunction "2_2") (pintype "passive"))
      (node (ref "C18") (pin "2") (pinfunction "2_2") (pintype "passive"))
      (node (ref "C19") (pin "2") (pinfunction "2_2") (pintype "passive"))
      (node (ref "C20") (pin "2") (pinfunction "2_2") (pintype "passive"))
      (node (ref "C21") (pin "2") (pinfunction "2_2") (pintype "passive"))
      (node (ref "C22") (pin "2") (pinfunction "2_2") (pintype "passive"))
      (node (ref "C23") (pin "2") (pinfunction "2_2") (pintype "passive"))
      (node (ref "C24") (pin "2") (pinfunction "2_2") (pintype "passive"))
      (node (ref "C25") (pin "2") (pinfunction "2_2") (pintype "passive"))
      (node (ref "C26") (pin "2") (pinfunction "2_2") (pintype "passive"))
      (node (ref "C27") (pin "2") (pinfunction "2_2") (pintype "passive"))
      (node (ref "C28") (pin "2") (pinfunction "2_2") (pintype "passive"))
      (node (ref "C29") (pin "2") (pinfunction "2_2") (pintype "passive"))
      (node (ref "C30") (pin "2") (pinfunction "2_2") (pintype "passive"))
      (node (ref "C31") (pin "2") (pinfunction "2_2") (pintype "passive"))
      (node (ref "C32") (pin "2") (pinfunction "2_2") (pintype "passive"))
      (node (ref "C33") (pin "-") (pinfunction "-_-") (pintype "passive"))
      (node (ref "C34") (pin "2") (pinfunction "2_2") (pintype "passive"))
      (node (ref "C35") (pin "-") (pinfunction "-_-") (pintype "passive"))
      (node (ref "C36") (pin "-") (pinfunction "-_-") (pintype "passive"))
      (node (ref "C5") (pin "1") (pinfunction "1_1") (pintype "passive"))
      (node (ref "C6") (pin "2") (pinfunction "2_2") (pintype "passive"))
      (node (ref "C7") (pin "2") (pinfunction "2_2") (pintype "passive"))
      (node (ref "C8") (pin "2") (pinfunction "2_2") (pintype "passive"))
      (node (ref "C9") (pin "2") (pinfunction "2_2") (pintype "passive"))
      (node (ref "IC1") (pin "11") (pinfunction "GND_11") (pintype "bidirectional"))
      (node (ref "IC2") (pin "4") (pinfunction "GND_4") (pintype "power_in"))
      (node (ref "IC3") (pin "3") (pinfunction "GND_3") (pintype "bidirectional"))
      (node (ref "JP1") (pin "1") (pinfunction "1_1") (pintype "passive"))
      (node (ref "JP3") (pin "6") (pinfunction "6_6") (pintype "passive"))
      (node (ref "R12") (pin "1") (pinfunction "1_1") (pintype "passive"))
      (node (ref "R17") (pin "1") (pinfunction "1_1") (pintype "passive"))
      (node (ref "R19") (pin "1") (pinfunction "1_1") (pintype "passive"))
      (node (ref "R21") (pin "1") (pinfunction "1_1") (pintype "passive"))
      (node (ref "REG1.2") (pin "1") (pinfunction "GND_1") (pintype "bidirectional"))
      (node (ref "REG2.5") (pin "1") (pinfunction "GND_1") (pintype "bidirectional"))
      (node (ref "RESET_SW") (pin "2") (pinfunction "2_2") (pintype "passive"))
      (node (ref "SV1") (pin "12") (pinfunction "12_12") (pintype "passive"))
      (node (ref "SV1") (pin "2") (pinfunction "2_2") (pintype "passive"))
      (node (ref "U$1") (pin "P24") (pinfunction "VSS_P24") (pintype "bidirectional"))
      (node (ref "U$1") (pin "P30") (pinfunction "CE_P30") (pintype "bidirectional"))
      (node (ref "U$2") (pin "GND") (pinfunction "GND_GND") (pintype "power_in"))
      (node (ref "U$4") (pin "1") (pinfunction "GND_1") (pintype "bidirectional"))
      (node (ref "U$5") (pin "1") (pinfunction "GND_1") (pintype "bidirectional"))
      (node (ref "U$6") (pin "P24") (pinfunction "VSS_P24") (pintype "bidirectional"))
      (node (ref "U$6") (pin "P30") (pinfunction "CE_P30") (pintype "bidirectional"))
      (node (ref "U1") (pin "P101") (pinfunction "GND11_P101") (pintype "passive"))
      (node (ref "U1") (pin "P114") (pinfunction "GND12_P114") (pintype "passive"))
      (node (ref "U1") (pin "P117") (pinfunction "GND13_P117") (pintype "passive"))
      (node (ref "U1") (pin "P136") (pinfunction "GND14_P136") (pintype "passive"))
      (node (ref "U1") (pin "P139") (pinfunction "GND15_P139") (pintype "passive"))
      (node (ref "U1") (pin "P16") (pinfunction "GND1_P16") (pintype "passive"))
      (node (ref "U1") (pin "P22") (pinfunction "GND2_P22") (pintype "passive"))
      (node (ref "U1") (pin "P29") (pinfunction "GND3_P29") (pintype "passive"))
      (node (ref "U1") (pin "P37") (pinfunction "M1_P37") (pintype "bidirectional"))
      (node (ref "U1") (pin "P38") (pinfunction "M0_P38") (pintype "bidirectional"))
      (node (ref "U1") (pin "P39") (pinfunction "M2_P39") (pintype "bidirectional"))
      (node (ref "U1") (pin "P42") (pinfunction "GND4_P42") (pintype "passive"))
      (node (ref "U1") (pin "P45") (pinfunction "GND5_P45") (pintype "passive"))
      (node (ref "U1") (pin "P64") (pinfunction "GND6_P64") (pintype "passive"))
      (node (ref "U1") (pin "P67") (pinfunction "GND7_P67") (pintype "passive"))
      (node (ref "U1") (pin "P81") (pinfunction "GND8_P81") (pintype "passive"))
      (node (ref "U1") (pin "P88") (pinfunction "GND9_P88") (pintype "passive"))
      (node (ref "U1") (pin "P9") (pinfunction "GND0_P9") (pintype "passive"))
      (node (ref "U1") (pin "P94") (pinfunction "GND10_P94") (pintype "passive"))
      (node (ref "X1") (pin "3") (pinfunction "2_3") (pintype "passive"))
      (node (ref "X2") (pin "13") (pinfunction "13_13") (pintype "passive"))
      (node (ref "X2") (pin "14") (pinfunction "14_14") (pintype "passive"))
      (node (ref "X2") (pin "17") (pinfunction "17_17") (pintype "passive"))
      (node (ref "X2") (pin "18") (pinfunction "18_18") (pintype "passive"))
      (node (ref "X2") (pin "21") (pinfunction "21_21") (pintype "passive"))
      (node (ref "X2") (pin "4") (pinfunction "4_4") (pintype "passive"))
      (node (ref "X2") (pin "5") (pinfunction "5_5") (pintype "passive"))
      (node (ref "X2") (pin "9") (pinfunction "9_9") (pintype "passive"))
      (node (ref "X3") (pin "3") (pinfunction "3_3") (pintype "passive"))
      (node (ref "X3") (pin "SH1") (pinfunction "PE1_SH1") (pintype "power_in"))
      (node (ref "X3") (pin "SH2") (pinfunction "PE2_SH2") (pintype "power_in"))
      (node (ref "X3") (pin "SH3") (pinfunction "PE3_SH3") (pintype "power_in"))
      (node (ref "X4") (pin "8") (pinfunction "F_8") (pintype "passive"))
      (node (ref "X4") (pin "G1") (pinfunction "G1_G1") (pintype "passive"))
      (node (ref "X5") (pin "8") (pinfunction "F_8") (pintype "passive"))
      (node (ref "X5") (pin "G1") (pinfunction "G1_G1") (pintype "passive"))
      (node (ref "X7") (pin "3") (pinfunction "3_3") (pintype "power_in"))
    )
    (net (code "69") (name "Net-(C1-Pad2)") (class "Default")
      (node (ref "C1") (pin "2") (pinfunction "2_2") (pintype "passive"))
      (node (ref "R23") (pin "2") (pinfunction "2_2") (pintype "passive"))
      (node (ref "R48") (pin "1") (pinfunction "1_1") (pintype "passive"))
    )
    (net (code "70") (name "Net-(C2-Pad1)") (class "Default")
      (node (ref "C2") (pin "1") (pinfunction "1_1") (pintype "passive"))
      (node (ref "R17") (pin "2") (pinfunction "2_2") (pintype "passive"))
      (node (ref "X1") (pin "1") (pinfunction "1_1") (pintype "passive"))
    )
    (net (code "71") (name "Net-(C3-Pad1)") (class "Default")
      (node (ref "C3") (pin "1") (pinfunction "1_1") (pintype "passive"))
      (node (ref "R48") (pin "2") (pinfunction "2_2") (pintype "passive"))
    )
    (net (code "72") (name "Net-(C4-Pad1)") (class "Default")
      (node (ref "C4") (pin "1") (pinfunction "1_1") (pintype "passive"))
      (node (ref "R49") (pin "2") (pinfunction "2_2") (pintype "passive"))
    )
    (net (code "73") (name "Net-(C5-Pad2)") (class "Default")
      (node (ref "C5") (pin "2") (pinfunction "2_2") (pintype "passive"))
      (node (ref "R34") (pin "2") (pinfunction "2_2") (pintype "passive"))
      (node (ref "R49") (pin "1") (pinfunction "1_1") (pintype "passive"))
    )
    (net (code "74") (name "Net-(IC1-CLK)") (class "Default")
      (node (ref "IC1") (pin "3") (pinfunction "CLK_3") (pintype "bidirectional"))
      (node (ref "U1") (pin "P72") (pinfunction "CCLK_P72") (pintype "bidirectional"))
    )
    (net (code "75") (name "Net-(IC1-TDI)") (class "Default")
      (node (ref "IC1") (pin "4") (pinfunction "TDI_4") (pintype "bidirectional"))
      (node (ref "U1") (pin "P109") (pinfunction "TDO_P109") (pintype "bidirectional"))
    )
    (net (code "76") (name "Net-(IC1-{slash}CE)") (class "Default")
      (node (ref "IC1") (pin "10") (pinfunction "/CE_10") (pintype "bidirectional"))
      (node (ref "U1") (pin "P71") (pinfunction "DONE_P71") (pintype "bidirectional"))
    )
    (net (code "77") (name "Net-(IC1-{slash}CF)") (class "Default")
      (node (ref "IC1") (pin "7") (pinfunction "/CF_7") (pintype "bidirectional"))
      (node (ref "U1") (pin "P143") (pinfunction "PROG_B_P143") (pintype "bidirectional"))
    )
    (net (code "78") (name "Net-(IC3-D+)") (class "Default")
      (node (ref "IC3") (pin "29") (pinfunction "D+_29") (pintype "bidirectional"))
      (node (ref "R54") (pin "2") (pinfunction "2_2") (pintype "passive"))
    )
    (net (code "79") (name "Net-(IC3-D-)") (class "Default")
      (node (ref "IC3") (pin "30") (pinfunction "D-_30") (pintype "bidirectional"))
      (node (ref "R53") (pin "2") (pinfunction "2_2") (pintype "passive"))
    )
    (net (code "80") (name "Net-(IC3-UGND)") (class "Default")
      (node (ref "IC3") (pin "28") (pinfunction "UGND_28") (pintype "bidirectional"))
      (node (ref "X6") (pin "4") (pinfunction "4_4") (pintype "passive"))
    )
    (net (code "81") (name "Net-(Q5-B)") (class "Default")
      (node (ref "Q5") (pin "1") (pinfunction "B_1") (pintype "passive"))
      (node (ref "R8") (pin "2") (pinfunction "2_2") (pintype "passive"))
    )
    (net (code "82") (name "Net-(Q5-E)") (class "Default")
      (node (ref "Q5") (pin "2") (pinfunction "E_2") (pintype "passive"))
      (node (ref "R13") (pin "2") (pinfunction "2_2") (pintype "passive"))
      (node (ref "R14") (pin "2") (pinfunction "2_2") (pintype "passive"))
    )
    (net (code "83") (name "Net-(Q6-B)") (class "Default")
      (node (ref "Q6") (pin "1") (pinfunction "B_1") (pintype "passive"))
      (node (ref "R10") (pin "2") (pinfunction "2_2") (pintype "passive"))
      (node (ref "R9") (pin "2") (pinfunction "2_2") (pintype "passive"))
    )
    (net (code "84") (name "Net-(Q6-E)") (class "Default")
      (node (ref "Q6") (pin "2") (pinfunction "E_2") (pintype "passive"))
      (node (ref "R15") (pin "2") (pinfunction "2_2") (pintype "passive"))
      (node (ref "R16") (pin "2") (pinfunction "2_2") (pintype "passive"))
      (node (ref "R20") (pin "2") (pinfunction "2_2") (pintype "passive"))
    )
    (net (code "85") (name "Net-(Q7-B)") (class "Default")
      (node (ref "Q7") (pin "1") (pinfunction "B_1") (pintype "passive"))
      (node (ref "R29") (pin "2") (pinfunction "2_2") (pintype "passive"))
      (node (ref "R30") (pin "2") (pinfunction "2_2") (pintype "passive"))
    )
    (net (code "86") (name "Net-(Q7-E)") (class "Default")
      (node (ref "Q7") (pin "2") (pinfunction "E_2") (pintype "passive"))
      (node (ref "R31") (pin "2") (pinfunction "2_2") (pintype "passive"))
      (node (ref "R32") (pin "2") (pinfunction "2_2") (pintype "passive"))
      (node (ref "R33") (pin "2") (pinfunction "2_2") (pintype "passive"))
    )
    (net (code "87") (name "Net-(Q8-B)") (class "Default")
      (node (ref "Q8") (pin "1") (pinfunction "B_1") (pintype "passive"))
      (node (ref "R24") (pin "2") (pinfunction "2_2") (pintype "passive"))
      (node (ref "R25") (pin "2") (pinfunction "2_2") (pintype "passive"))
    )
    (net (code "88") (name "Net-(Q8-E)") (class "Default")
      (node (ref "Q8") (pin "2") (pinfunction "E_2") (pintype "passive"))
      (node (ref "R26") (pin "2") (pinfunction "2_2") (pintype "passive"))
      (node (ref "R27") (pin "2") (pinfunction "2_2") (pintype "passive"))
      (node (ref "R28") (pin "2") (pinfunction "2_2") (pintype "passive"))
    )
    (net (code "89") (name "Net-(R18-Pad2)") (class "Default")
      (node (ref "R18") (pin "2") (pinfunction "2_2") (pintype "passive"))
      (node (ref "R22") (pin "2") (pinfunction "2_2") (pintype "passive"))
    )
    (net (code "90") (name "Net-(R53-Pad1)") (class "Default")
      (node (ref "R53") (pin "1") (pinfunction "1_1") (pintype "passive"))
      (node (ref "X6") (pin "2") (pinfunction "2_2") (pintype "passive"))
    )
    (net (code "91") (name "Net-(R54-Pad1)") (class "Default")
      (node (ref "R54") (pin "1") (pinfunction "1_1") (pintype "passive"))
      (node (ref "X6") (pin "3") (pinfunction "3_3") (pintype "passive"))
    )
    (net (code "92") (name "Net-(T2-B)") (class "Default")
      (node (ref "C2") (pin "2") (pinfunction "2_2") (pintype "passive"))
      (node (ref "R18") (pin "1") (pinfunction "1_1") (pintype "passive"))
      (node (ref "R19") (pin "2") (pinfunction "2_2") (pintype "passive"))
      (node (ref "T2") (pin "1") (pinfunction "B_1") (pintype "passive"))
    )
    (net (code "93") (name "Net-(U$1-A0)") (class "Default")
      (node (ref "U$1") (pin "P20") (pinfunction "A0_P20") (pintype "bidirectional"))
      (node (ref "U1") (pin "P77") (pinfunction "IO_L20P_3_P77") (pintype "bidirectional"))
    )
    (net (code "94") (name "Net-(U$1-A1)") (class "Default")
      (node (ref "U$1") (pin "P19") (pinfunction "A1_P19") (pintype "bidirectional"))
      (node (ref "U1") (pin "P76") (pinfunction "IO_P76") (pintype "bidirectional"))
    )
    (net (code "95") (name "Net-(U$1-A2)") (class "Default")
      (node (ref "U$1") (pin "P18") (pinfunction "A2_P18") (pintype "bidirectional"))
      (node (ref "U1") (pin "P74") (pinfunction "IO_L01N_3VRP_3_P74") (pintype "bidirectional"))
    )
    (net (code "96") (name "Net-(U$1-A3)") (class "Default")
      (node (ref "U$1") (pin "P17") (pinfunction "A3_P17") (pintype "bidirectional"))
      (node (ref "U1") (pin "P73") (pinfunction "IO_L01P_3VRN_3_P73") (pintype "bidirectional"))
    )
    (net (code "97") (name "Net-(U$1-A4)") (class "Default")
      (node (ref "U$1") (pin "P16") (pinfunction "A4_P16") (pintype "bidirectional"))
      (node (ref "U1") (pin "P108") (pinfunction "IO_L01N_2VRP_2_P108") (pintype "bidirectional"))
    )
    (net (code "98") (name "Net-(U$1-A5)") (class "Default")
      (node (ref "U$1") (pin "P15") (pinfunction "A5_P15") (pintype "bidirectional"))
      (node (ref "U1") (pin "P107") (pinfunction "IO_L01P_2VRN_2_P107") (pintype "bidirectional"))
    )
    (net (code "99") (name "Net-(U$1-A6)") (class "Default")
      (node (ref "U$1") (pin "P14") (pinfunction "A6_P14") (pintype "bidirectional"))
      (node (ref "U1") (pin "P105") (pinfunction "IO_L20N_2_P105") (pintype "bidirectional"))
    )
    (net (code "100") (name "Net-(U$1-A7)") (class "Default")
      (node (ref "U$1") (pin "P13") (pinfunction "A7_P13") (pintype "bidirectional"))
      (node (ref "U1") (pin "P104") (pinfunction "IO_L20P_2_P104") (pintype "bidirectional"))
    )
    (net (code "101") (name "Net-(U$1-A8)") (class "Default")
      (node (ref "U$1") (pin "P3") (pinfunction "A8_P3") (pintype "bidirectional"))
      (node (ref "U1") (pin "P93") (pinfunction "IO_L40N_2_P93") (pintype "bidirectional"))
    )
    (net (code "102") (name "Net-(U$1-A9)") (class "Default")
      (node (ref "U$1") (pin "P2") (pinfunction "A9_P2") (pintype "bidirectional"))
      (node (ref "U1") (pin "P92") (pinfunction "IO_L40P_2VREF_2_P92") (pintype "bidirectional"))
    )
    (net (code "103") (name "Net-(U$1-A10)") (class "Default")
      (node (ref "U$1") (pin "P31") (pinfunction "A10_P31") (pintype "bidirectional"))
      (node (ref "U1") (pin "P87") (pinfunction "IO_L24N_3_P87") (pintype "bidirectional"))
    )
    (net (code "104") (name "Net-(U$1-A11)") (class "Default")
      (node (ref "U$1") (pin "P1") (pinfunction "A11_P1") (pintype "bidirectional"))
      (node (ref "U1") (pin "P90") (pinfunction "IO_L40N_3VREF_3_P90") (pintype "bidirectional"))
    )
    (net (code "105") (name "Net-(U$1-A12)") (class "Default")
      (node (ref "U$1") (pin "P12") (pinfunction "A12_P12") (pintype "bidirectional"))
      (node (ref "U1") (pin "P103") (pinfunction "IO_L21N_2_P103") (pintype "bidirectional"))
    )
    (net (code "106") (name "Net-(U$1-A13)") (class "Default")
      (node (ref "U$1") (pin "P4") (pinfunction "A13_P4") (pintype "bidirectional"))
      (node (ref "U1") (pin "P95") (pinfunction "IO_L24P_2_P95") (pintype "bidirectional"))
    )
    (net (code "107") (name "Net-(U$1-A14)") (class "Default")
      (node (ref "U$1") (pin "P11") (pinfunction "A14_P11") (pintype "bidirectional"))
      (node (ref "U1") (pin "P102") (pinfunction "IO_L21P_2_P102") (pintype "bidirectional"))
    )
    (net (code "108") (name "Net-(U$1-A15)") (class "Default")
      (node (ref "U$1") (pin "P7") (pinfunction "A15_P7") (pintype "bidirectional"))
      (node (ref "U1") (pin "P98") (pinfunction "IO_L23N_2VREF_2_P98") (pintype "bidirectional"))
    )
    (net (code "109") (name "Net-(U$1-A16)") (class "Default")
      (node (ref "U$1") (pin "P10") (pinfunction "A16_P10") (pintype "bidirectional"))
      (node (ref "U1") (pin "P100") (pinfunction "IO_L22N_2_P100") (pintype "bidirectional"))
    )
    (net (code "110") (name "Net-(U$1-A17)") (class "Default")
      (node (ref "U$1") (pin "P6") (pinfunction "A17_P6") (pintype "bidirectional"))
      (node (ref "U1") (pin "P97") (pinfunction "IO_L23P_2_P97") (pintype "bidirectional"))
    )
    (net (code "111") (name "Net-(U$1-A18)") (class "Default")
      (node (ref "U$1") (pin "P9") (pinfunction "A18_P9") (pintype "bidirectional"))
      (node (ref "U1") (pin "P99") (pinfunction "IO_L22P_2_P99") (pintype "bidirectional"))
    )
    (net (code "112") (name "Net-(U$1-DQ0)") (class "Default")
      (node (ref "U$1") (pin "P21") (pinfunction "DQ0_P21") (pintype "bidirectional"))
      (node (ref "U1") (pin "P78") (pinfunction "IO_L20N_3_P78") (pintype "bidirectional"))
    )
    (net (code "113") (name "Net-(U$1-DQ1)") (class "Default")
      (node (ref "U$1") (pin "P22") (pinfunction "DQ1_P22") (pintype "bidirectional"))
      (node (ref "U1") (pin "P79") (pinfunction "IO_L21P_3_P79") (pintype "bidirectional"))
    )
    (net (code "114") (name "Net-(U$1-DQ2)") (class "Default")
      (node (ref "U$1") (pin "P23") (pinfunction "DQ2_P23") (pintype "bidirectional"))
      (node (ref "U1") (pin "P80") (pinfunction "IO_L21N_3_P80") (pintype "bidirectional"))
    )
    (net (code "115") (name "Net-(U$1-DQ3)") (class "Default")
      (node (ref "U$1") (pin "P25") (pinfunction "DQ3_P25") (pintype "bidirectional"))
      (node (ref "U1") (pin "P82") (pinfunction "IO_L22P_3_P82") (pintype "bidirectional"))
    )
    (net (code "116") (name "Net-(U$1-DQ4)") (class "Default")
      (node (ref "U$1") (pin "P26") (pinfunction "DQ4_P26") (pintype "bidirectional"))
      (node (ref "U1") (pin "P83") (pinfunction "IO_L22N_3_P83") (pintype "bidirectional"))
    )
    (net (code "117") (name "Net-(U$1-DQ5)") (class "Default")
      (node (ref "U$1") (pin "P27") (pinfunction "DQ5_P27") (pintype "bidirectional"))
      (node (ref "U1") (pin "P84") (pinfunction "IO_L23P_3VREF_3_P84") (pintype "bidirectional"))
    )
    (net (code "118") (name "Net-(U$1-DQ6)") (class "Default")
      (node (ref "U$1") (pin "P28") (pinfunction "DQ6_P28") (pintype "bidirectional"))
      (node (ref "U1") (pin "P85") (pinfunction "IO_L23N_3_P85") (pintype "bidirectional"))
    )
    (net (code "119") (name "Net-(U$1-DQ7)") (class "Default")
      (node (ref "U$1") (pin "P29") (pinfunction "DQ7_P29") (pintype "bidirectional"))
      (node (ref "U1") (pin "P86") (pinfunction "IO_L24P_3_P86") (pintype "bidirectional"))
    )
    (net (code "120") (name "Net-(U$1-OE)") (class "Default")
      (node (ref "U$1") (pin "P32") (pinfunction "OE_P32") (pintype "bidirectional"))
      (node (ref "U1") (pin "P89") (pinfunction "IO_L40P_3_P89") (pintype "bidirectional"))
    )
    (net (code "121") (name "Net-(U$1-WE)") (class "Default")
      (node (ref "U$1") (pin "P5") (pinfunction "WE_P5") (pintype "bidirectional"))
      (node (ref "U1") (pin "P96") (pinfunction "IO_L24N_2_P96") (pintype "bidirectional"))
    )
    (net (code "122") (name "Net-(U$6-A0)") (class "Default")
      (node (ref "U$6") (pin "P20") (pinfunction "A0_P20") (pintype "bidirectional"))
      (node (ref "U1") (pin "P24") (pinfunction "IO_L24N_6VREF_6_P24") (pintype "bidirectional"))
    )
    (net (code "123") (name "Net-(U$6-A1)") (class "Default")
      (node (ref "U$6") (pin "P19") (pinfunction "A1_P19") (pintype "bidirectional"))
      (node (ref "U1") (pin "P23") (pinfunction "IO_L24P_6_P23") (pintype "bidirectional"))
    )
    (net (code "124") (name "Net-(U$6-A2)") (class "Default")
      (node (ref "U$6") (pin "P18") (pinfunction "A2_P18") (pintype "bidirectional"))
      (node (ref "U1") (pin "P21") (pinfunction "IO_L40N_6_P21") (pintype "bidirectional"))
    )
    (net (code "125") (name "Net-(U$6-A3)") (class "Default")
      (node (ref "U$6") (pin "P17") (pinfunction "A3_P17") (pintype "bidirectional"))
      (node (ref "U1") (pin "P20") (pinfunction "IO_L40P_6VREF_6_P20") (pintype "bidirectional"))
    )
    (net (code "126") (name "Net-(U$6-A4)") (class "Default")
      (node (ref "U$6") (pin "P16") (pinfunction "A4_P16") (pintype "bidirectional"))
      (node (ref "U1") (pin "P18") (pinfunction "IO_L40N_7VREF_7_P18") (pintype "bidirectional"))
    )
    (net (code "127") (name "Net-(U$6-A5)") (class "Default")
      (node (ref "U$6") (pin "P15") (pinfunction "A5_P15") (pintype "bidirectional"))
      (node (ref "U1") (pin "P17") (pinfunction "IO_L40P_7_P17") (pintype "bidirectional"))
    )
    (net (code "128") (name "Net-(U$6-A6)") (class "Default")
      (node (ref "U$6") (pin "P14") (pinfunction "A6_P14") (pintype "bidirectional"))
      (node (ref "U1") (pin "P15") (pinfunction "IO_L24N_7_P15") (pintype "bidirectional"))
    )
    (net (code "129") (name "Net-(U$6-A7)") (class "Default")
      (node (ref "U$6") (pin "P13") (pinfunction "A7_P13") (pintype "bidirectional"))
      (node (ref "U1") (pin "P14") (pinfunction "IO_L24P_7_P14") (pintype "bidirectional"))
    )
    (net (code "130") (name "Net-(U$6-A8)") (class "Default")
      (node (ref "U$6") (pin "P3") (pinfunction "A8_P3") (pintype "bidirectional"))
      (node (ref "U1") (pin "P4") (pinfunction "IOVREF_7_P4") (pintype "bidirectional"))
    )
    (net (code "131") (name "Net-(U$6-A9)") (class "Default")
      (node (ref "U$6") (pin "P2") (pinfunction "A9_P2") (pintype "bidirectional"))
      (node (ref "U1") (pin "P2") (pinfunction "IO_L01N_7VRP_7_P2") (pintype "bidirectional"))
    )
    (net (code "132") (name "Net-(U$6-A10)") (class "Default")
      (node (ref "U$6") (pin "P31") (pinfunction "A10_P31") (pintype "bidirectional"))
      (node (ref "U1") (pin "P35") (pinfunction "IO_L01P_6VRN_6_P35") (pintype "bidirectional"))
    )
    (net (code "133") (name "Net-(U$6-A11)") (class "Default")
      (node (ref "U$6") (pin "P1") (pinfunction "A11_P1") (pintype "bidirectional"))
      (node (ref "U1") (pin "P1") (pinfunction "IO_L01P_7VRN_7_P1") (pintype "bidirectional"))
    )
    (net (code "134") (name "Net-(U$6-A12)") (class "Default")
      (node (ref "U$6") (pin "P12") (pinfunction "A12_P12") (pintype "bidirectional"))
      (node (ref "U1") (pin "P13") (pinfunction "IO_L23N_7_P13") (pintype "bidirectional"))
    )
    (net (code "135") (name "Net-(U$6-A13)") (class "Default")
      (node (ref "U$6") (pin "P4") (pinfunction "A13_P4") (pintype "bidirectional"))
      (node (ref "U1") (pin "P5") (pinfunction "IO_L20P_7_P5") (pintype "bidirectional"))
    )
    (net (code "136") (name "Net-(U$6-A14)") (class "Default")
      (node (ref "U$6") (pin "P11") (pinfunction "A14_P11") (pintype "bidirectional"))
      (node (ref "U1") (pin "P12") (pinfunction "IO_L23P_7_P12") (pintype "bidirectional"))
    )
    (net (code "137") (name "Net-(U$6-A15)") (class "Default")
      (node (ref "U$6") (pin "P7") (pinfunction "A15_P7") (pintype "bidirectional"))
      (node (ref "U1") (pin "P8") (pinfunction "IO_L21N_7_P8") (pintype "bidirectional"))
    )
    (net (code "138") (name "Net-(U$6-A16)") (class "Default")
      (node (ref "U$6") (pin "P10") (pinfunction "A16_P10") (pintype "bidirectional"))
      (node (ref "U1") (pin "P11") (pinfunction "IO_L22N_7_P11") (pintype "bidirectional"))
    )
    (net (code "139") (name "Net-(U$6-A17)") (class "Default")
      (node (ref "U$6") (pin "P6") (pinfunction "A17_P6") (pintype "bidirectional"))
      (node (ref "U1") (pin "P7") (pinfunction "IO_L21P_7_P7") (pintype "bidirectional"))
    )
    (net (code "140") (name "Net-(U$6-A18)") (class "Default")
      (node (ref "U$6") (pin "P9") (pinfunction "A18_P9") (pintype "bidirectional"))
      (node (ref "U1") (pin "P10") (pinfunction "IO_L22P_7_P10") (pintype "bidirectional"))
    )
    (net (code "141") (name "Net-(U$6-DQ0)") (class "Default")
      (node (ref "U$6") (pin "P21") (pinfunction "DQ0_P21") (pintype "bidirectional"))
      (node (ref "U1") (pin "P25") (pinfunction "IO_L23P_6_P25") (pintype "bidirectional"))
    )
    (net (code "142") (name "Net-(U$6-DQ1)") (class "Default")
      (node (ref "U$6") (pin "P22") (pinfunction "DQ1_P22") (pintype "bidirectional"))
      (node (ref "U1") (pin "P26") (pinfunction "IO_L23N_6_P26") (pintype "bidirectional"))
    )
    (net (code "143") (name "Net-(U$6-DQ2)") (class "Default")
      (node (ref "U$6") (pin "P23") (pinfunction "DQ2_P23") (pintype "bidirectional"))
      (node (ref "U1") (pin "P27") (pinfunction "IO_L22P_6_P27") (pintype "bidirectional"))
    )
    (net (code "144") (name "Net-(U$6-DQ3)") (class "Default")
      (node (ref "U$6") (pin "P25") (pinfunction "DQ3_P25") (pintype "bidirectional"))
      (node (ref "U1") (pin "P28") (pinfunction "IO_L22N_6_P28") (pintype "bidirectional"))
    )
    (net (code "145") (name "Net-(U$6-DQ4)") (class "Default")
      (node (ref "U$6") (pin "P26") (pinfunction "DQ4_P26") (pintype "bidirectional"))
      (node (ref "U1") (pin "P30") (pinfunction "IO_L21P_6_P30") (pintype "bidirectional"))
    )
    (net (code "146") (name "Net-(U$6-DQ5)") (class "Default")
      (node (ref "U$6") (pin "P27") (pinfunction "DQ5_P27") (pintype "bidirectional"))
      (node (ref "U1") (pin "P31") (pinfunction "IO_L21N_6_P31") (pintype "bidirectional"))
    )
    (net (code "147") (name "Net-(U$6-DQ6)") (class "Default")
      (node (ref "U$6") (pin "P28") (pinfunction "DQ6_P28") (pintype "bidirectional"))
      (node (ref "U1") (pin "P32") (pinfunction "IO_L20P_6_P32") (pintype "bidirectional"))
    )
    (net (code "148") (name "Net-(U$6-DQ7)") (class "Default")
      (node (ref "U$6") (pin "P29") (pinfunction "DQ7_P29") (pintype "bidirectional"))
      (node (ref "U1") (pin "P33") (pinfunction "IO_L20N_6_P33") (pintype "bidirectional"))
    )
    (net (code "149") (name "Net-(U$6-OE)") (class "Default")
      (node (ref "U$6") (pin "P32") (pinfunction "OE_P32") (pintype "bidirectional"))
      (node (ref "U1") (pin "P36") (pinfunction "IO_L01N_6VRP_6_P36") (pintype "bidirectional"))
    )
    (net (code "150") (name "Net-(U$6-WE)") (class "Default")
      (node (ref "U$6") (pin "P5") (pinfunction "WE_P5") (pintype "bidirectional"))
      (node (ref "U1") (pin "P6") (pinfunction "IO_L20N_7_P6") (pintype "bidirectional"))
    )
    (net (code "151") (name "Net-(U1G-IO_L32P_4GCLK0)") (class "Default")
      (node (ref "SV1") (pin "10") (pinfunction "10_10") (pintype "passive"))
      (node (ref "U1") (pin "P55") (pinfunction "IO_L32P_4GCLK0_P55") (pintype "bidirectional"))
    )
    (net (code "152") (name "Net-(U1N-TCK)") (class "Default")
      (node (ref "R2") (pin "1") (pinfunction "1_1") (pintype "passive"))
      (node (ref "U1") (pin "P110") (pinfunction "TCK_P110") (pintype "bidirectional"))
    )
    (net (code "153") (name "Net-(U1N-TDI)") (class "Default")
      (node (ref "R1") (pin "1") (pinfunction "1_1") (pintype "passive"))
      (node (ref "U1") (pin "P144") (pinfunction "TDI_P144") (pintype "bidirectional"))
    )
    (net (code "154") (name "Net-(U1N-TMS)") (class "Default")
      (node (ref "R3") (pin "1") (pinfunction "1_1") (pintype "passive"))
      (node (ref "U1") (pin "P111") (pinfunction "TMS_P111") (pintype "bidirectional"))
    )
    (net (code "155") (name "Net-(X4A-F)") (class "Default")
      (node (ref "R40") (pin "2") (pinfunction "2_2") (pintype "passive"))
      (node (ref "X4") (pin "1") (pinfunction "F_1") (pintype "passive"))
    )
    (net (code "156") (name "Net-(X4B-F)") (class "Default")
      (node (ref "R41") (pin "2") (pinfunction "2_2") (pintype "passive"))
      (node (ref "X4") (pin "2") (pinfunction "F_2") (pintype "passive"))
    )
    (net (code "157") (name "Net-(X4C-F)") (class "Default")
      (node (ref "R42") (pin "2") (pinfunction "2_2") (pintype "passive"))
      (node (ref "X4") (pin "3") (pinfunction "F_3") (pintype "passive"))
    )
    (net (code "158") (name "Net-(X4D-F)") (class "Default")
      (node (ref "R43") (pin "2") (pinfunction "2_2") (pintype "passive"))
      (node (ref "X4") (pin "4") (pinfunction "F_4") (pintype "passive"))
    )
    (net (code "159") (name "Net-(X4F-F)") (class "Default")
      (node (ref "R44") (pin "2") (pinfunction "2_2") (pintype "passive"))
      (node (ref "X4") (pin "6") (pinfunction "F_6") (pintype "passive"))
    )
    (net (code "160") (name "Net-(X4G-F)") (class "Default")
      (node (ref "R45") (pin "2") (pinfunction "2_2") (pintype "passive"))
      (node (ref "X4") (pin "7") (pinfunction "F_7") (pintype "passive"))
    )
    (net (code "161") (name "Net-(X5A-F)") (class "Default")
      (node (ref "R46") (pin "1") (pinfunction "1_1") (pintype "passive"))
      (node (ref "X5") (pin "1") (pinfunction "F_1") (pintype "passive"))
    )
    (net (code "162") (name "Net-(X5B-F)") (class "Default")
      (node (ref "R39") (pin "1") (pinfunction "1_1") (pintype "passive"))
      (node (ref "X5") (pin "2") (pinfunction "F_2") (pintype "passive"))
    )
    (net (code "163") (name "Net-(X5C-F)") (class "Default")
      (node (ref "R38") (pin "1") (pinfunction "1_1") (pintype "passive"))
      (node (ref "X5") (pin "3") (pinfunction "F_3") (pintype "passive"))
    )
    (net (code "164") (name "Net-(X5D-F)") (class "Default")
      (node (ref "R37") (pin "1") (pinfunction "1_1") (pintype "passive"))
      (node (ref "X5") (pin "4") (pinfunction "F_4") (pintype "passive"))
    )
    (net (code "165") (name "Net-(X5F-F)") (class "Default")
      (node (ref "R36") (pin "1") (pinfunction "1_1") (pintype "passive"))
      (node (ref "X5") (pin "6") (pinfunction "F_6") (pintype "passive"))
    )
    (net (code "166") (name "Net-(X5G-F)") (class "Default")
      (node (ref "R35") (pin "1") (pinfunction "1_1") (pintype "passive"))
      (node (ref "X5") (pin "7") (pinfunction "F_7") (pintype "passive"))
    )
    (net (code "167") (name "unconnected-(IC1-NC.1-Pad2)") (class "Default")
      (node (ref "IC1") (pin "2") (pinfunction "NC.1_2") (pintype "bidirectional"))
    )
    (net (code "168") (name "unconnected-(IC1-NC.2-Pad9)") (class "Default")
      (node (ref "IC1") (pin "9") (pinfunction "NC.2_9") (pintype "bidirectional"))
    )
    (net (code "169") (name "unconnected-(IC1-NC.3-Pad12)") (class "Default")
      (node (ref "IC1") (pin "12") (pinfunction "NC.3_12") (pintype "bidirectional"))
    )
    (net (code "170") (name "unconnected-(IC1-NC.4-Pad14)") (class "Default")
      (node (ref "IC1") (pin "14") (pinfunction "NC.4_14") (pintype "bidirectional"))
    )
    (net (code "171") (name "unconnected-(IC1-NC.5-Pad15)") (class "Default")
      (node (ref "IC1") (pin "15") (pinfunction "NC.5_15") (pintype "bidirectional"))
    )
    (net (code "172") (name "unconnected-(IC1-NC.6-Pad16)") (class "Default")
      (node (ref "IC1") (pin "16") (pinfunction "NC.6_16") (pintype "bidirectional"))
    )
    (net (code "173") (name "unconnected-(IC1-{slash}CEO-Pad13)") (class "Default")
      (node (ref "IC1") (pin "13") (pinfunction "/CEO_13") (pintype "bidirectional"))
    )
    (net (code "174") (name "unconnected-(IC3-PC2(AIN2{slash}PCIN11)-Pad5)") (class "Default")
      (node (ref "IC3") (pin "5") (pinfunction "PC2(AIN2/PCIN11)_5") (pintype "bidirectional"))
    )
    (net (code "175") (name "unconnected-(IC3-PC4(PCINT10)-Pad26)") (class "Default")
      (node (ref "IC3") (pin "26") (pinfunction "PC4(PCINT10)_26") (pintype "bidirectional"))
    )
    (net (code "176") (name "unconnected-(IC3-PC5(OC1B{slash}PCINT9)-Pad25)") (class "Default")
      (node (ref "IC3") (pin "25") (pinfunction "PC5(OC1B/PCINT9)_25") (pintype "bidirectional"))
    )
    (net (code "177") (name "unconnected-(IC3-PC6(OC1A{slash}PCINT8)-Pad23)") (class "Default")
      (node (ref "IC3") (pin "23") (pinfunction "PC6(OC1A/PCINT8)_23") (pintype "bidirectional"))
    )
    (net (code "178") (name "unconnected-(IC3-PD0(INT0{slash}OC0B)-Pad6)") (class "Default")
      (node (ref "IC3") (pin "6") (pinfunction "PD0(INT0/OC0B)_6") (pintype "bidirectional"))
    )
    (net (code "179") (name "unconnected-(IC3-PD1(INT1{slash}AIN0)-Pad7)") (class "Default")
      (node (ref "IC3") (pin "7") (pinfunction "PD1(INT1/AIN0)_7") (pintype "bidirectional"))
    )
    (net (code "180") (name "unconnected-(IC3-PD4(INT5{slash}AIN3)-Pad10)") (class "Default")
      (node (ref "IC3") (pin "10") (pinfunction "PD4(INT5/AIN3)_10") (pintype "bidirectional"))
    )
    (net (code "181") (name "unconnected-(IC3-PD5(XCK{slash}AIN4{slash}PCINT12)-Pad11)") (class "Default")
      (node (ref "IC3") (pin "11") (pinfunction "PD5(XCK/AIN4/PCINT12)_11") (pintype "bidirectional"))
    )
    (net (code "182") (name "unconnected-(IC3-PD6(INT6{slash}AIN5{slash}RTS)-Pad12)") (class "Default")
      (node (ref "IC3") (pin "12") (pinfunction "PD6(INT6/AIN5/RTS)_12") (pintype "bidirectional"))
    )
    (net (code "183") (name "unconnected-(IC3-UCAP-Pad27)") (class "Default")
      (node (ref "IC3") (pin "27") (pinfunction "UCAP_27") (pintype "bidirectional"))
    )
    (net (code "184") (name "unconnected-(IC3-XTAL1-Pad1)") (class "Default")
      (node (ref "IC3") (pin "1") (pinfunction "XTAL1_1") (pintype "bidirectional"))
    )
    (net (code "185") (name "unconnected-(IC3-XTAL2{slash}PC0-Pad2)") (class "Default")
      (node (ref "IC3") (pin "2") (pinfunction "XTAL2/PC0_2") (pintype "bidirectional"))
    )
    (net (code "186") (name "unconnected-(IC3-{slash}RESET(PC1)-Pad24)") (class "Default")
      (node (ref "IC3") (pin "24") (pinfunction "/RESET(PC1)_24") (pintype "bidirectional"))
    )
    (net (code "187") (name "unconnected-(JP1-Pad3)") (class "Default")
      (node (ref "JP1") (pin "3") (pinfunction "3_3") (pintype "passive"))
    )
    (net (code "188") (name "unconnected-(JP1-Pad4)") (class "Default")
      (node (ref "JP1") (pin "4") (pinfunction "4_4") (pintype "passive"))
    )
    (net (code "189") (name "unconnected-(JP1-Pad5)") (class "Default")
      (node (ref "JP1") (pin "5") (pinfunction "5_5") (pintype "passive"))
    )
    (net (code "190") (name "unconnected-(JP1-Pad6)") (class "Default")
      (node (ref "JP1") (pin "6") (pinfunction "6_6") (pintype "passive"))
    )
    (net (code "191") (name "unconnected-(JP1-Pad7)") (class "Default")
      (node (ref "JP1") (pin "7") (pinfunction "7_7") (pintype "passive"))
    )
    (net (code "192") (name "unconnected-(JP1-Pad8)") (class "Default")
      (node (ref "JP1") (pin "8") (pinfunction "8_8") (pintype "passive"))
    )
    (net (code "193") (name "unconnected-(JP1-Pad9)") (class "Default")
      (node (ref "JP1") (pin "9") (pinfunction "9_9") (pintype "passive"))
    )
    (net (code "194") (name "unconnected-(JP1-Pad10)") (class "Default")
      (node (ref "JP1") (pin "10") (pinfunction "10_10") (pintype "passive"))
    )
    (net (code "195") (name "unconnected-(JP1-Pad11)") (class "Default")
      (node (ref "JP1") (pin "11") (pinfunction "11_11") (pintype "passive"))
    )
    (net (code "196") (name "unconnected-(JP1-Pad12)") (class "Default")
      (node (ref "JP1") (pin "12") (pinfunction "12_12") (pintype "passive"))
    )
    (net (code "197") (name "unconnected-(JP1-Pad13)") (class "Default")
      (node (ref "JP1") (pin "13") (pinfunction "13_13") (pintype "passive"))
    )
    (net (code "198") (name "unconnected-(JP1-Pad14)") (class "Default")
      (node (ref "JP1") (pin "14") (pinfunction "14_14") (pintype "passive"))
    )
    (net (code "199") (name "unconnected-(JP1-Pad15)") (class "Default")
      (node (ref "JP1") (pin "15") (pinfunction "15_15") (pintype "passive"))
    )
    (net (code "200") (name "unconnected-(JP1-Pad16)") (class "Default")
      (node (ref "JP1") (pin "16") (pinfunction "16_16") (pintype "passive"))
    )
    (net (code "201") (name "unconnected-(JP1-Pad17)") (class "Default")
      (node (ref "JP1") (pin "17") (pinfunction "17_17") (pintype "passive"))
    )
    (net (code "202") (name "unconnected-(JP1-Pad18)") (class "Default")
      (node (ref "JP1") (pin "18") (pinfunction "18_18") (pintype "passive"))
    )
    (net (code "203") (name "unconnected-(JP1-Pad19)") (class "Default")
      (node (ref "JP1") (pin "19") (pinfunction "19_19") (pintype "passive"))
    )
    (net (code "204") (name "unconnected-(JP1-Pad20)") (class "Default")
      (node (ref "JP1") (pin "20") (pinfunction "20_20") (pintype "passive"))
    )
    (net (code "205") (name "unconnected-(JP2-Pad1)") (class "Default")
      (node (ref "JP2") (pin "1") (pinfunction "1_1") (pintype "passive"))
    )
    (net (code "206") (name "unconnected-(JP2-Pad2)") (class "Default")
      (node (ref "JP2") (pin "2") (pinfunction "2_2") (pintype "passive"))
    )
    (net (code "207") (name "unconnected-(JP2-Pad3)") (class "Default")
      (node (ref "JP2") (pin "3") (pinfunction "3_3") (pintype "passive"))
    )
    (net (code "208") (name "unconnected-(JP2-Pad4)") (class "Default")
      (node (ref "JP2") (pin "4") (pinfunction "4_4") (pintype "passive"))
    )
    (net (code "209") (name "unconnected-(JP2-Pad5)") (class "Default")
      (node (ref "JP2") (pin "5") (pinfunction "5_5") (pintype "passive"))
    )
    (net (code "210") (name "unconnected-(JP2-Pad6)") (class "Default")
      (node (ref "JP2") (pin "6") (pinfunction "6_6") (pintype "passive"))
    )
    (net (code "211") (name "unconnected-(JP2-Pad7)") (class "Default")
      (node (ref "JP2") (pin "7") (pinfunction "7_7") (pintype "passive"))
    )
    (net (code "212") (name "unconnected-(JP2-Pad8)") (class "Default")
      (node (ref "JP2") (pin "8") (pinfunction "8_8") (pintype "passive"))
    )
    (net (code "213") (name "unconnected-(JP2-Pad9)") (class "Default")
      (node (ref "JP2") (pin "9") (pinfunction "9_9") (pintype "passive"))
    )
    (net (code "214") (name "unconnected-(JP2-Pad10)") (class "Default")
      (node (ref "JP2") (pin "10") (pinfunction "10_10") (pintype "passive"))
    )
    (net (code "215") (name "unconnected-(JP2-Pad11)") (class "Default")
      (node (ref "JP2") (pin "11") (pinfunction "11_11") (pintype "passive"))
    )
    (net (code "216") (name "unconnected-(JP2-Pad12)") (class "Default")
      (node (ref "JP2") (pin "12") (pinfunction "12_12") (pintype "passive"))
    )
    (net (code "217") (name "unconnected-(JP2-Pad13)") (class "Default")
      (node (ref "JP2") (pin "13") (pinfunction "13_13") (pintype "passive"))
    )
    (net (code "218") (name "unconnected-(JP2-Pad14)") (class "Default")
      (node (ref "JP2") (pin "14") (pinfunction "14_14") (pintype "passive"))
    )
    (net (code "219") (name "unconnected-(JP2-Pad15)") (class "Default")
      (node (ref "JP2") (pin "15") (pinfunction "15_15") (pintype "passive"))
    )
    (net (code "220") (name "unconnected-(JP2-Pad16)") (class "Default")
      (node (ref "JP2") (pin "16") (pinfunction "16_16") (pintype "passive"))
    )
    (net (code "221") (name "unconnected-(JP2-Pad17)") (class "Default")
      (node (ref "JP2") (pin "17") (pinfunction "17_17") (pintype "passive"))
    )
    (net (code "222") (name "unconnected-(JP2-Pad18)") (class "Default")
      (node (ref "JP2") (pin "18") (pinfunction "18_18") (pintype "passive"))
    )
    (net (code "223") (name "unconnected-(JP2-Pad19)") (class "Default")
      (node (ref "JP2") (pin "19") (pinfunction "19_19") (pintype "passive"))
    )
    (net (code "224") (name "unconnected-(JP2-Pad20)") (class "Default")
      (node (ref "JP2") (pin "20") (pinfunction "20_20") (pintype "passive"))
    )
    (net (code "225") (name "unconnected-(REG1.2-VOUT2-Pad2)") (class "Default")
      (node (ref "REG1.2") (pin "2") (pinfunction "VOUT2_2") (pintype "bidirectional"))
    )
    (net (code "226") (name "unconnected-(REG2.5-VOUT2-Pad2)") (class "Default")
      (node (ref "REG2.5") (pin "2") (pinfunction "VOUT2_2") (pintype "bidirectional"))
    )
    (net (code "227") (name "unconnected-(SV2-Pad1)") (class "Default")
      (node (ref "SV2") (pin "1") (pinfunction "1_1") (pintype "passive"))
    )
    (net (code "228") (name "unconnected-(SV2-Pad2)") (class "Default")
      (node (ref "SV2") (pin "2") (pinfunction "2_2") (pintype "passive"))
    )
    (net (code "229") (name "unconnected-(SV2-Pad3)") (class "Default")
      (node (ref "SV2") (pin "3") (pinfunction "3_3") (pintype "passive"))
    )
    (net (code "230") (name "unconnected-(SV2-Pad4)") (class "Default")
      (node (ref "SV2") (pin "4") (pinfunction "4_4") (pintype "passive"))
    )
    (net (code "231") (name "unconnected-(SV2-Pad5)") (class "Default")
      (node (ref "SV2") (pin "5") (pinfunction "5_5") (pintype "passive"))
    )
    (net (code "232") (name "unconnected-(SV2-Pad6)") (class "Default")
      (node (ref "SV2") (pin "6") (pinfunction "6_6") (pintype "passive"))
    )
    (net (code "233") (name "unconnected-(SV2-Pad7)") (class "Default")
      (node (ref "SV2") (pin "7") (pinfunction "7_7") (pintype "passive"))
    )
    (net (code "234") (name "unconnected-(SV2-Pad8)") (class "Default")
      (node (ref "SV2") (pin "8") (pinfunction "8_8") (pintype "passive"))
    )
    (net (code "235") (name "unconnected-(SV2-Pad9)") (class "Default")
      (node (ref "SV2") (pin "9") (pinfunction "9_9") (pintype "passive"))
    )
    (net (code "236") (name "unconnected-(SV2-Pad10)") (class "Default")
      (node (ref "SV2") (pin "10") (pinfunction "10_10") (pintype "passive"))
    )
    (net (code "237") (name "unconnected-(SV2-Pad11)") (class "Default")
      (node (ref "SV2") (pin "11") (pinfunction "11_11") (pintype "passive"))
    )
    (net (code "238") (name "unconnected-(SV2-Pad12)") (class "Default")
      (node (ref "SV2") (pin "12") (pinfunction "12_12") (pintype "passive"))
    )
    (net (code "239") (name "unconnected-(U$2-TRI-PadENA)") (class "Default")
      (node (ref "U$2") (pin "ENA") (pinfunction "TRI_ENA") (pintype "input"))
    )
    (net (code "240") (name "unconnected-(U$3-Pad1)") (class "Default")
      (node (ref "U$3") (pin "1") (pinfunction "1_1") (pintype "passive"))
    )
    (net (code "241") (name "unconnected-(U$3-Pad2)") (class "Default")
      (node (ref "U$3") (pin "2") (pinfunction "2_2") (pintype "passive"))
    )
    (net (code "242") (name "unconnected-(U$3-Pad3)") (class "Default")
      (node (ref "U$3") (pin "3") (pinfunction "3_3") (pintype "passive"))
    )
    (net (code "243") (name "unconnected-(U$3-Pad4)") (class "Default")
      (node (ref "U$3") (pin "4") (pinfunction "4_4") (pintype "passive"))
    )
    (net (code "244") (name "unconnected-(U$3-Pad5)") (class "Default")
      (node (ref "U$3") (pin "5") (pinfunction "5_5") (pintype "passive"))
    )
    (net (code "245") (name "unconnected-(U$3-Pad6)") (class "Default")
      (node (ref "U$3") (pin "6") (pinfunction "6_6") (pintype "passive"))
    )
    (net (code "246") (name "unconnected-(U$3-Pad7)") (class "Default")
      (node (ref "U$3") (pin "7") (pinfunction "7_7") (pintype "passive"))
    )
    (net (code "247") (name "unconnected-(U$3-Pad8)") (class "Default")
      (node (ref "U$3") (pin "8") (pinfunction "8_8") (pintype "passive"))
    )
    (net (code "248") (name "unconnected-(U$3-Pad9)") (class "Default")
      (node (ref "U$3") (pin "9") (pinfunction "9_9") (pintype "passive"))
    )
    (net (code "249") (name "unconnected-(U$3-Pad10)") (class "Default")
      (node (ref "U$3") (pin "10") (pinfunction "10_10") (pintype "passive"))
    )
    (net (code "250") (name "unconnected-(U$4-VOUT2-Pad2)") (class "Default")
      (node (ref "U$4") (pin "2") (pinfunction "VOUT2_2") (pintype "bidirectional"))
    )
    (net (code "251") (name "unconnected-(U1A-IO_L27P_0-PadP135)") (class "Default")
      (node (ref "U1") (pin "P135") (pinfunction "IO_L27P_0_P135") (pintype "bidirectional"))
    )
    (net (code "252") (name "unconnected-(U1A-IO_L30N_0-PadP132)") (class "Default")
      (node (ref "U1") (pin "P132") (pinfunction "IO_L30N_0_P132") (pintype "bidirectional"))
    )
    (net (code "253") (name "unconnected-(U1A-IO_L30P_0-PadP131)") (class "Default")
      (node (ref "U1") (pin "P131") (pinfunction "IO_L30P_0_P131") (pintype "bidirectional"))
    )
    (net (code "254") (name "unconnected-(U1A-IO_L31N_0-PadP130)") (class "Default")
      (node (ref "U1") (pin "P130") (pinfunction "IO_L31N_0_P130") (pintype "bidirectional"))
    )
    (net (code "255") (name "unconnected-(U1A-IO_L31P_0VREF_0-PadP129)") (class "Default")
      (node (ref "U1") (pin "P129") (pinfunction "IO_L31P_0VREF_0_P129") (pintype "bidirectional"))
    )
    (net (code "256") (name "unconnected-(U1A-IO_L32N_0GCLK7-PadP128)") (class "Default")
      (node (ref "U1") (pin "P128") (pinfunction "IO_L32N_0GCLK7_P128") (pintype "bidirectional"))
    )
    (net (code "257") (name "unconnected-(U1A-IO_L32P_0GCLK6-PadP127)") (class "Default")
      (node (ref "U1") (pin "P127") (pinfunction "IO_L32P_0GCLK6_P127") (pintype "bidirectional"))
    )
    (net (code "258") (name "unconnected-(U1C-IO-PadP116)") (class "Default")
      (node (ref "U1") (pin "P116") (pinfunction "IO_P116") (pintype "bidirectional"))
    )
    (net (code "259") (name "unconnected-(U1C-IO_L01N_1VRP_1-PadP113)") (class "Default")
      (node (ref "U1") (pin "P113") (pinfunction "IO_L01N_1VRP_1_P113") (pintype "bidirectional"))
    )
    (net (code "260") (name "unconnected-(U1C-IO_L01P_1VRN_1-PadP112)") (class "Default")
      (node (ref "U1") (pin "P112") (pinfunction "IO_L01P_1VRN_1_P112") (pintype "bidirectional"))
    )
    (net (code "261") (name "unconnected-(U1C-IO_L28N_1-PadP119)") (class "Default")
      (node (ref "U1") (pin "P119") (pinfunction "IO_L28N_1_P119") (pintype "bidirectional"))
    )
    (net (code "262") (name "unconnected-(U1C-IO_L28P_1-PadP118)") (class "Default")
      (node (ref "U1") (pin "P118") (pinfunction "IO_L28P_1_P118") (pintype "bidirectional"))
    )
    (net (code "263") (name "unconnected-(U1C-IO_L31N_1VREF_1-PadP123)") (class "Default")
      (node (ref "U1") (pin "P123") (pinfunction "IO_L31N_1VREF_1_P123") (pintype "bidirectional"))
    )
    (net (code "264") (name "unconnected-(U1C-IO_L31P_1-PadP122)") (class "Default")
      (node (ref "U1") (pin "P122") (pinfunction "IO_L31P_1_P122") (pintype "bidirectional"))
    )
    (net (code "265") (name "unconnected-(U1C-IO_L32N_1GCLK5-PadP125)") (class "Default")
      (node (ref "U1") (pin "P125") (pinfunction "IO_L32N_1GCLK5_P125") (pintype "bidirectional"))
    )
    (net (code "266") (name "unconnected-(U1C-IO_L32P_1GCLK4-PadP124)") (class "Default")
      (node (ref "U1") (pin "P124") (pinfunction "IO_L32P_1GCLK4_P124") (pintype "bidirectional"))
    )
    (net (code "267") (name "unconnected-(U1N-HSWAP_EN-PadP142)") (class "Default")
      (node (ref "U1") (pin "P142") (pinfunction "HSWAP_EN_P142") (pintype "bidirectional"))
    )
    (net (code "268") (name "unconnected-(X1-3-Pad2)") (class "Default")
      (node (ref "X1") (pin "2") (pinfunction "3_2") (pintype "passive"))
    )
    (net (code "269") (name "unconnected-(X2-Pad10)") (class "Default")
      (node (ref "X2") (pin "10") (pinfunction "10_10") (pintype "passive"))
    )
    (net (code "270") (name "unconnected-(X2-Pad12)") (class "Default")
      (node (ref "X2") (pin "12") (pinfunction "12_12") (pintype "passive"))
    )
    (net (code "271") (name "unconnected-(X3-Pad2)") (class "Default")
      (node (ref "X3") (pin "2") (pinfunction "2_2") (pintype "passive"))
    )
    (net (code "272") (name "unconnected-(X3-Pad8)") (class "Default")
      (node (ref "X3") (pin "8") (pinfunction "8_8") (pintype "passive"))
    )
    (net (code "273") (name "unconnected-(X4-PadG2)") (class "Default")
      (node (ref "X4") (pin "G2") (pinfunction "G2_G2") (pintype "passive"))
    )
    (net (code "274") (name "unconnected-(X5-PadG2)") (class "Default")
      (node (ref "X5") (pin "G2") (pinfunction "G2_G2") (pintype "passive"))
    )
    (net (code "275") (name "unconnected-(X6-Pad1)") (class "Default")
      (node (ref "X6") (pin "1") (pinfunction "1_1") (pintype "passive"))
    )
  )
)
